# clouds_v30.net
KiCad netlist of a schematic drawn in EAGLE
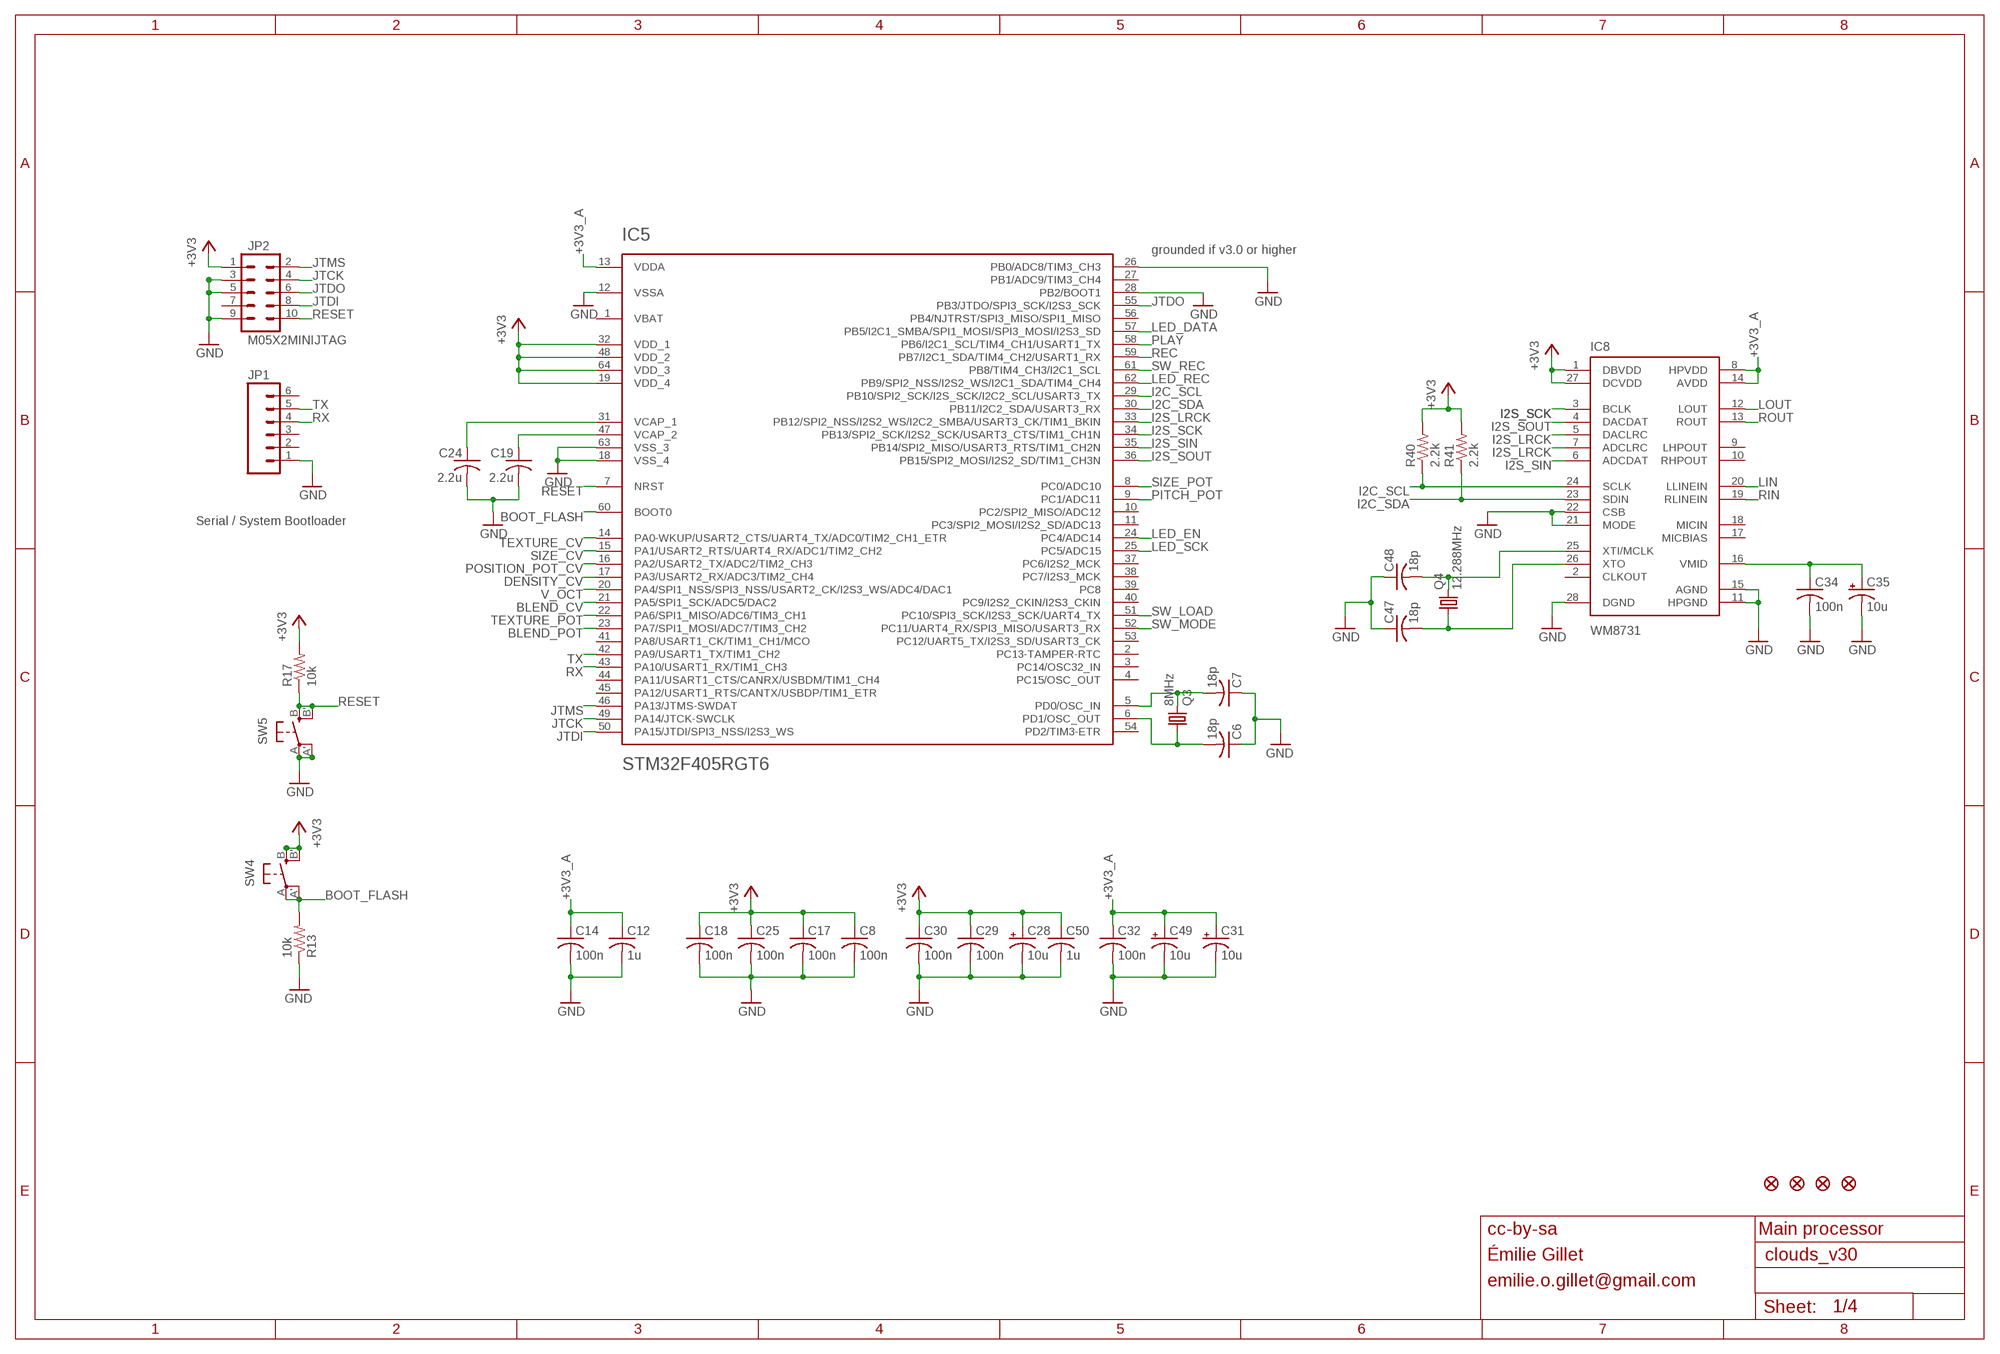
[diagram p0: schematic, sheet 1]
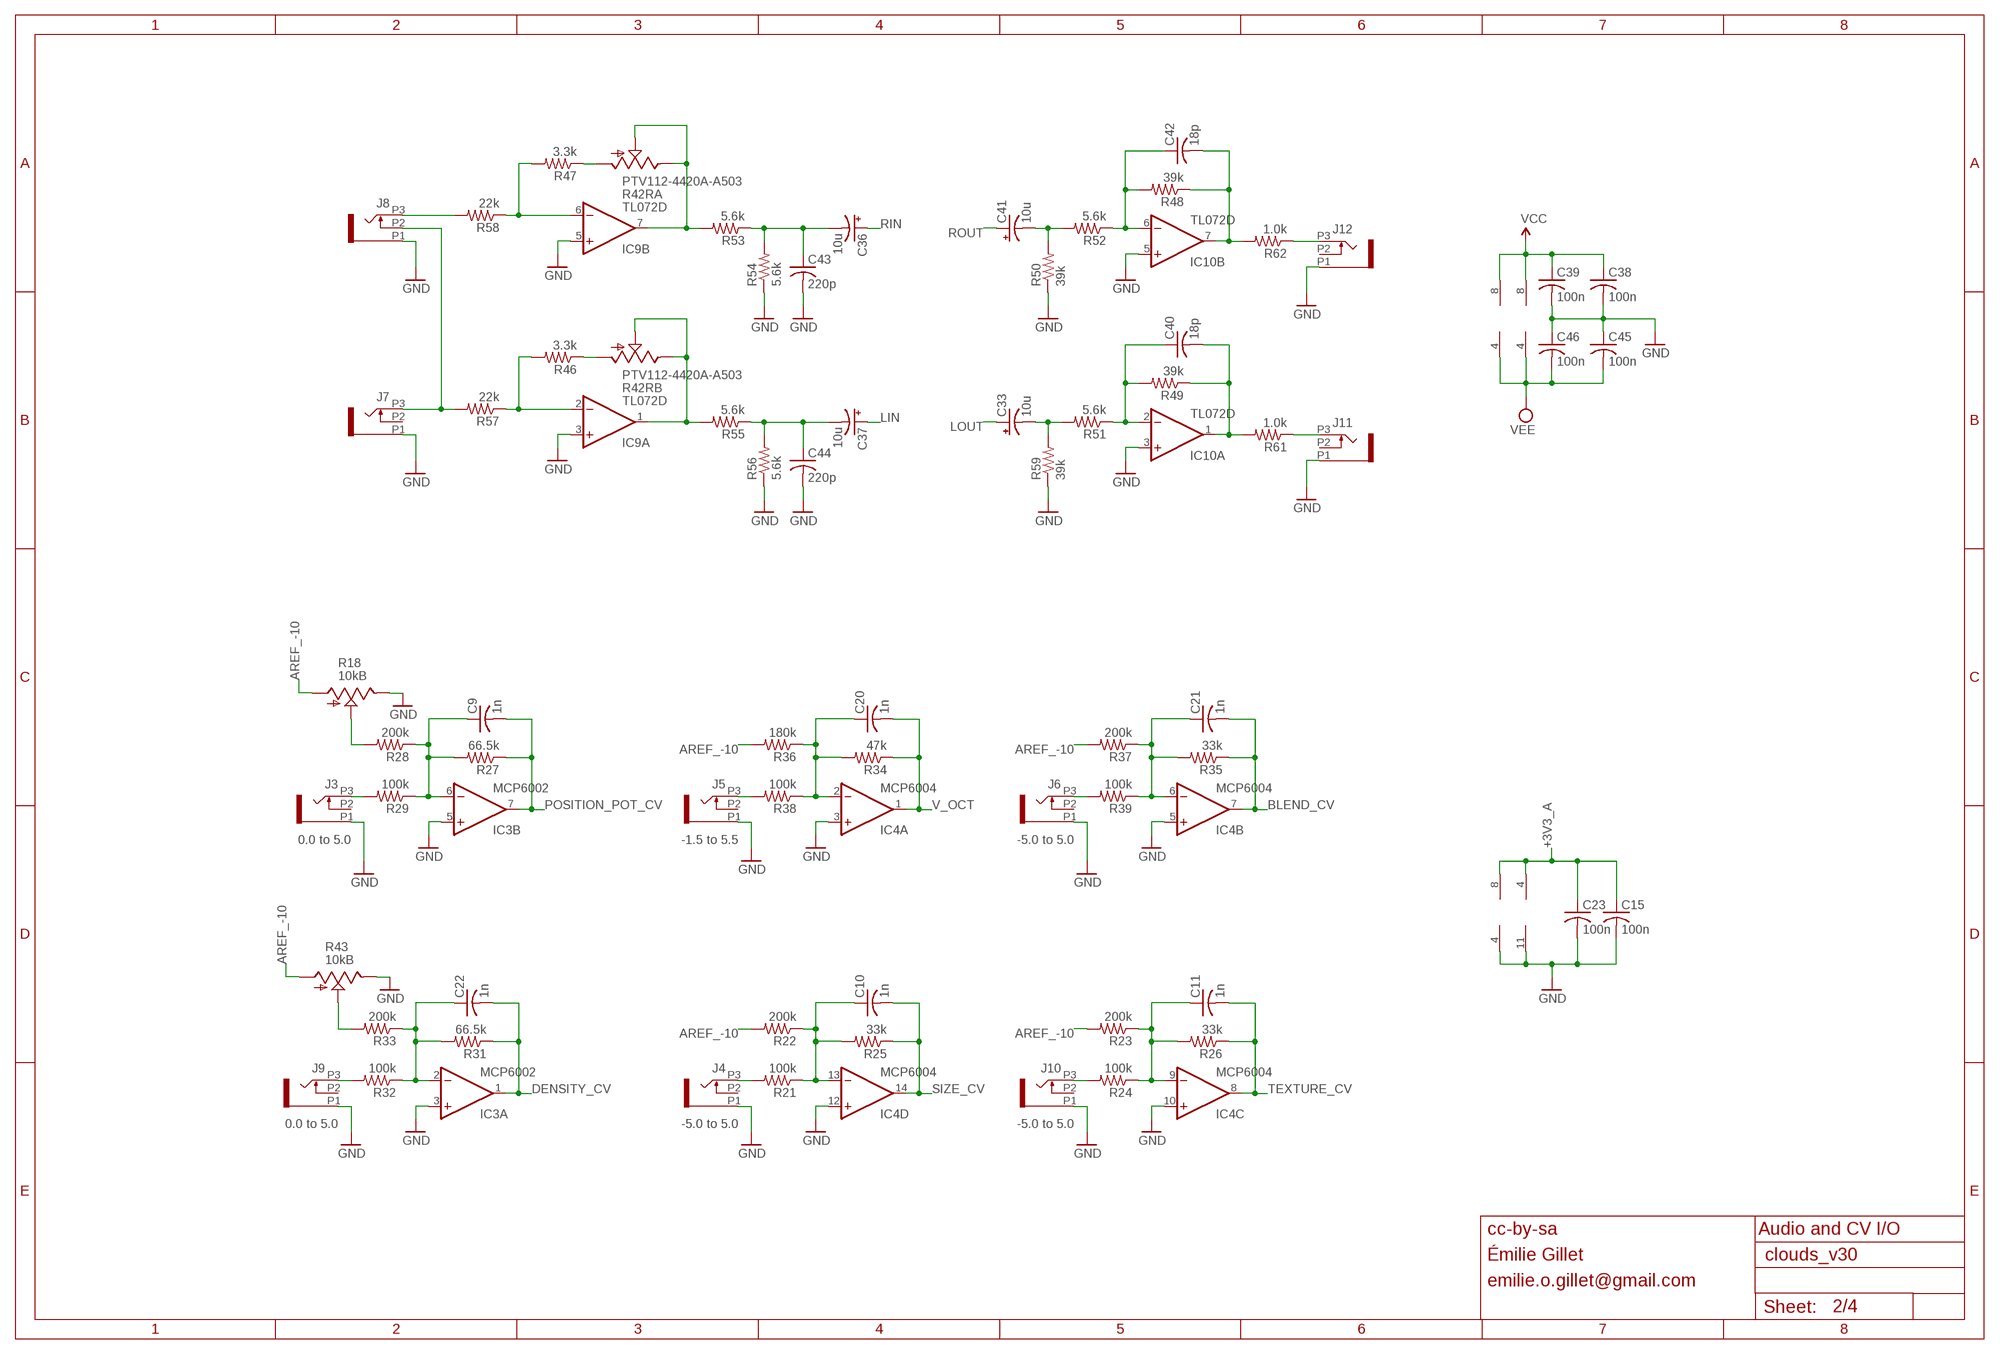
[diagram p1: schematic, sheet 2]
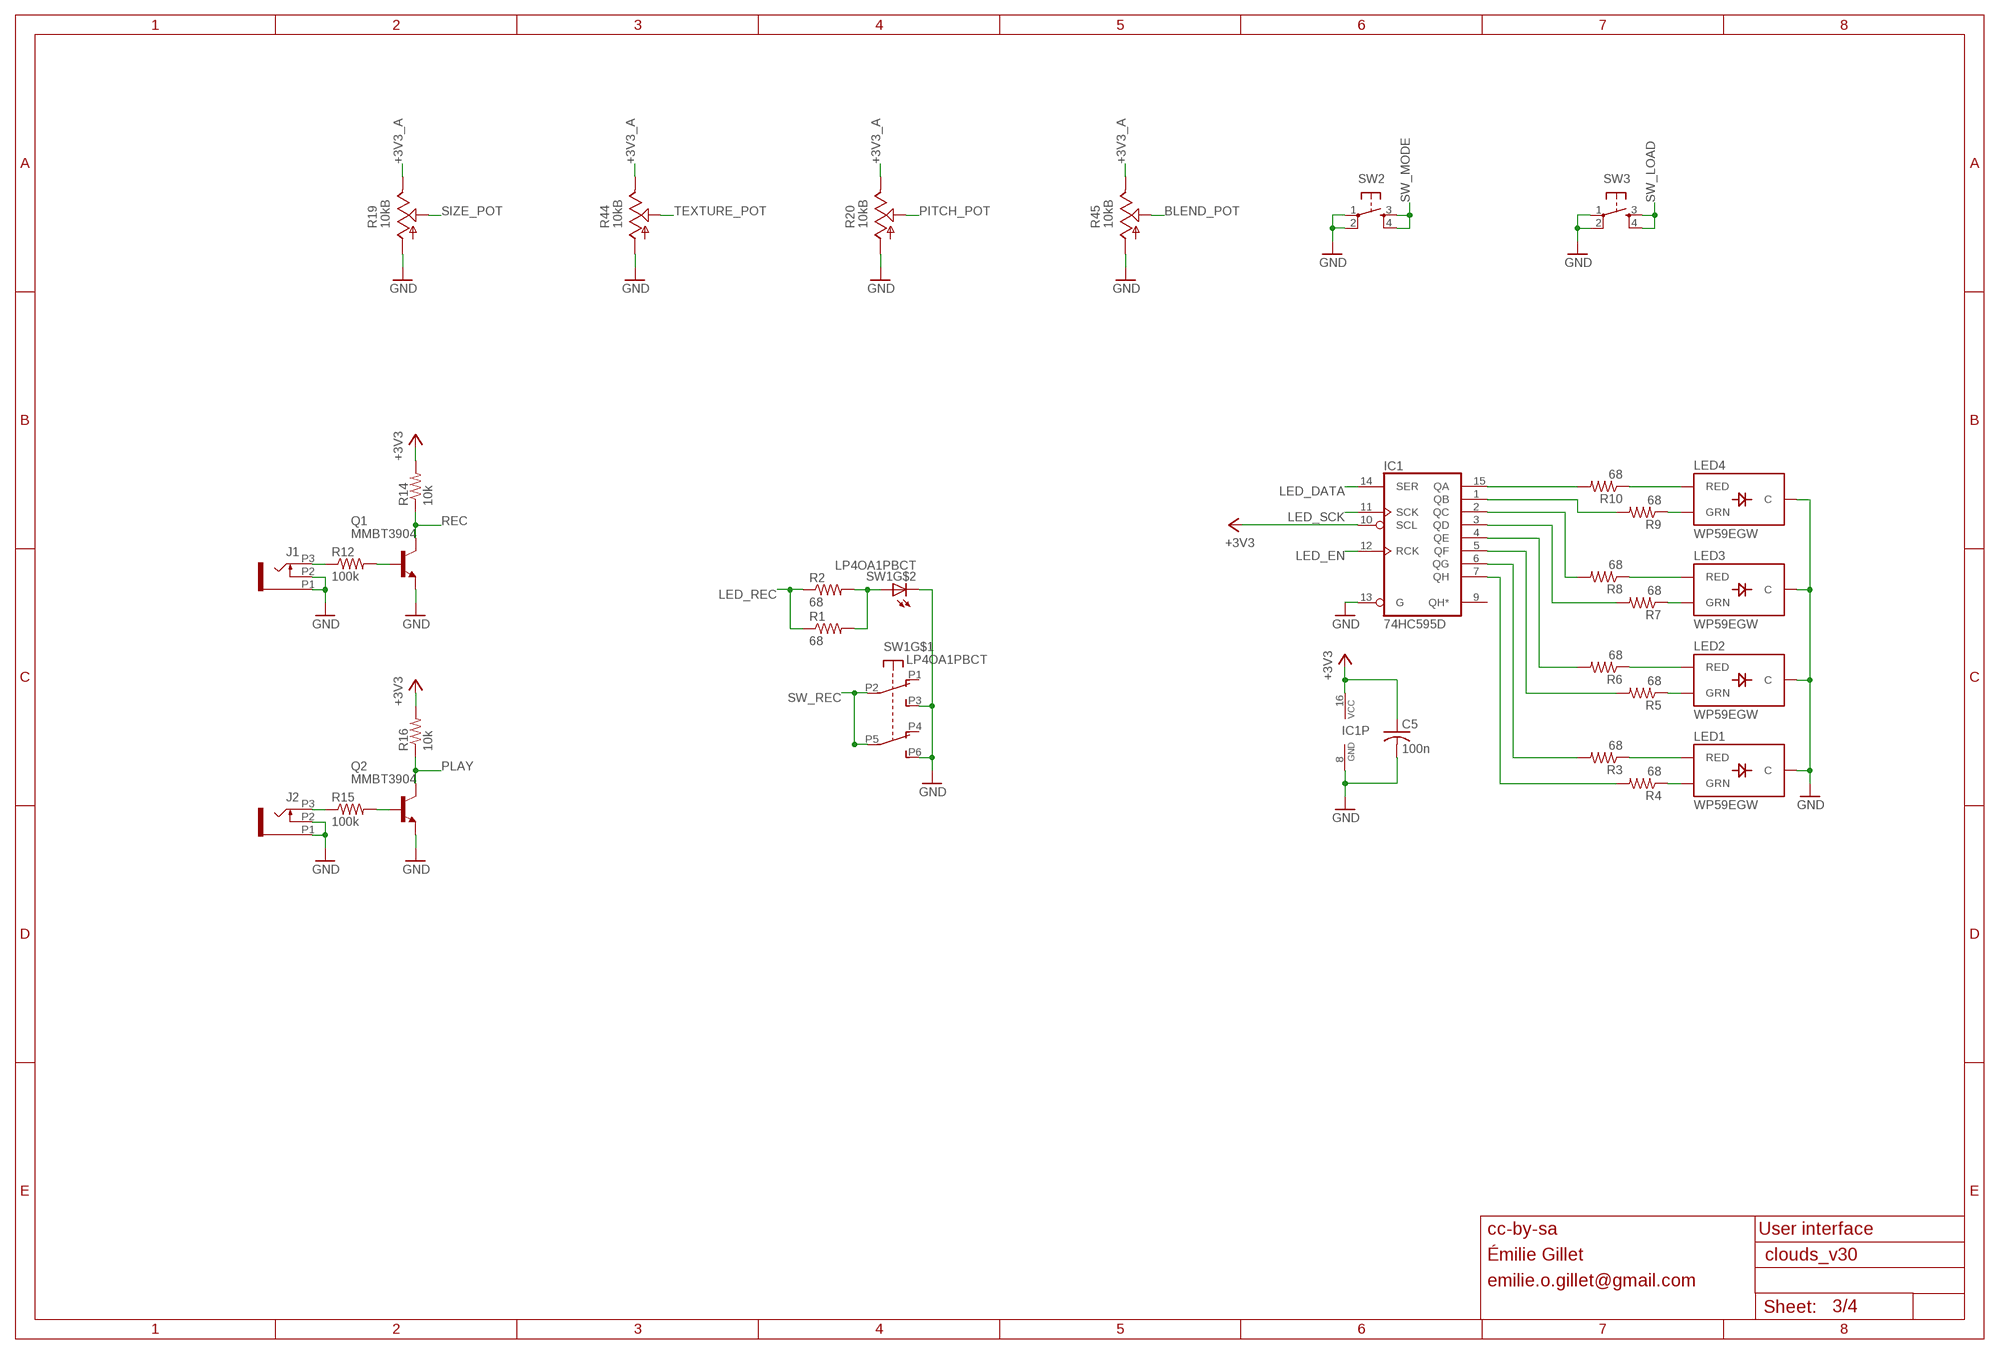
[diagram p2: schematic, sheet 3]
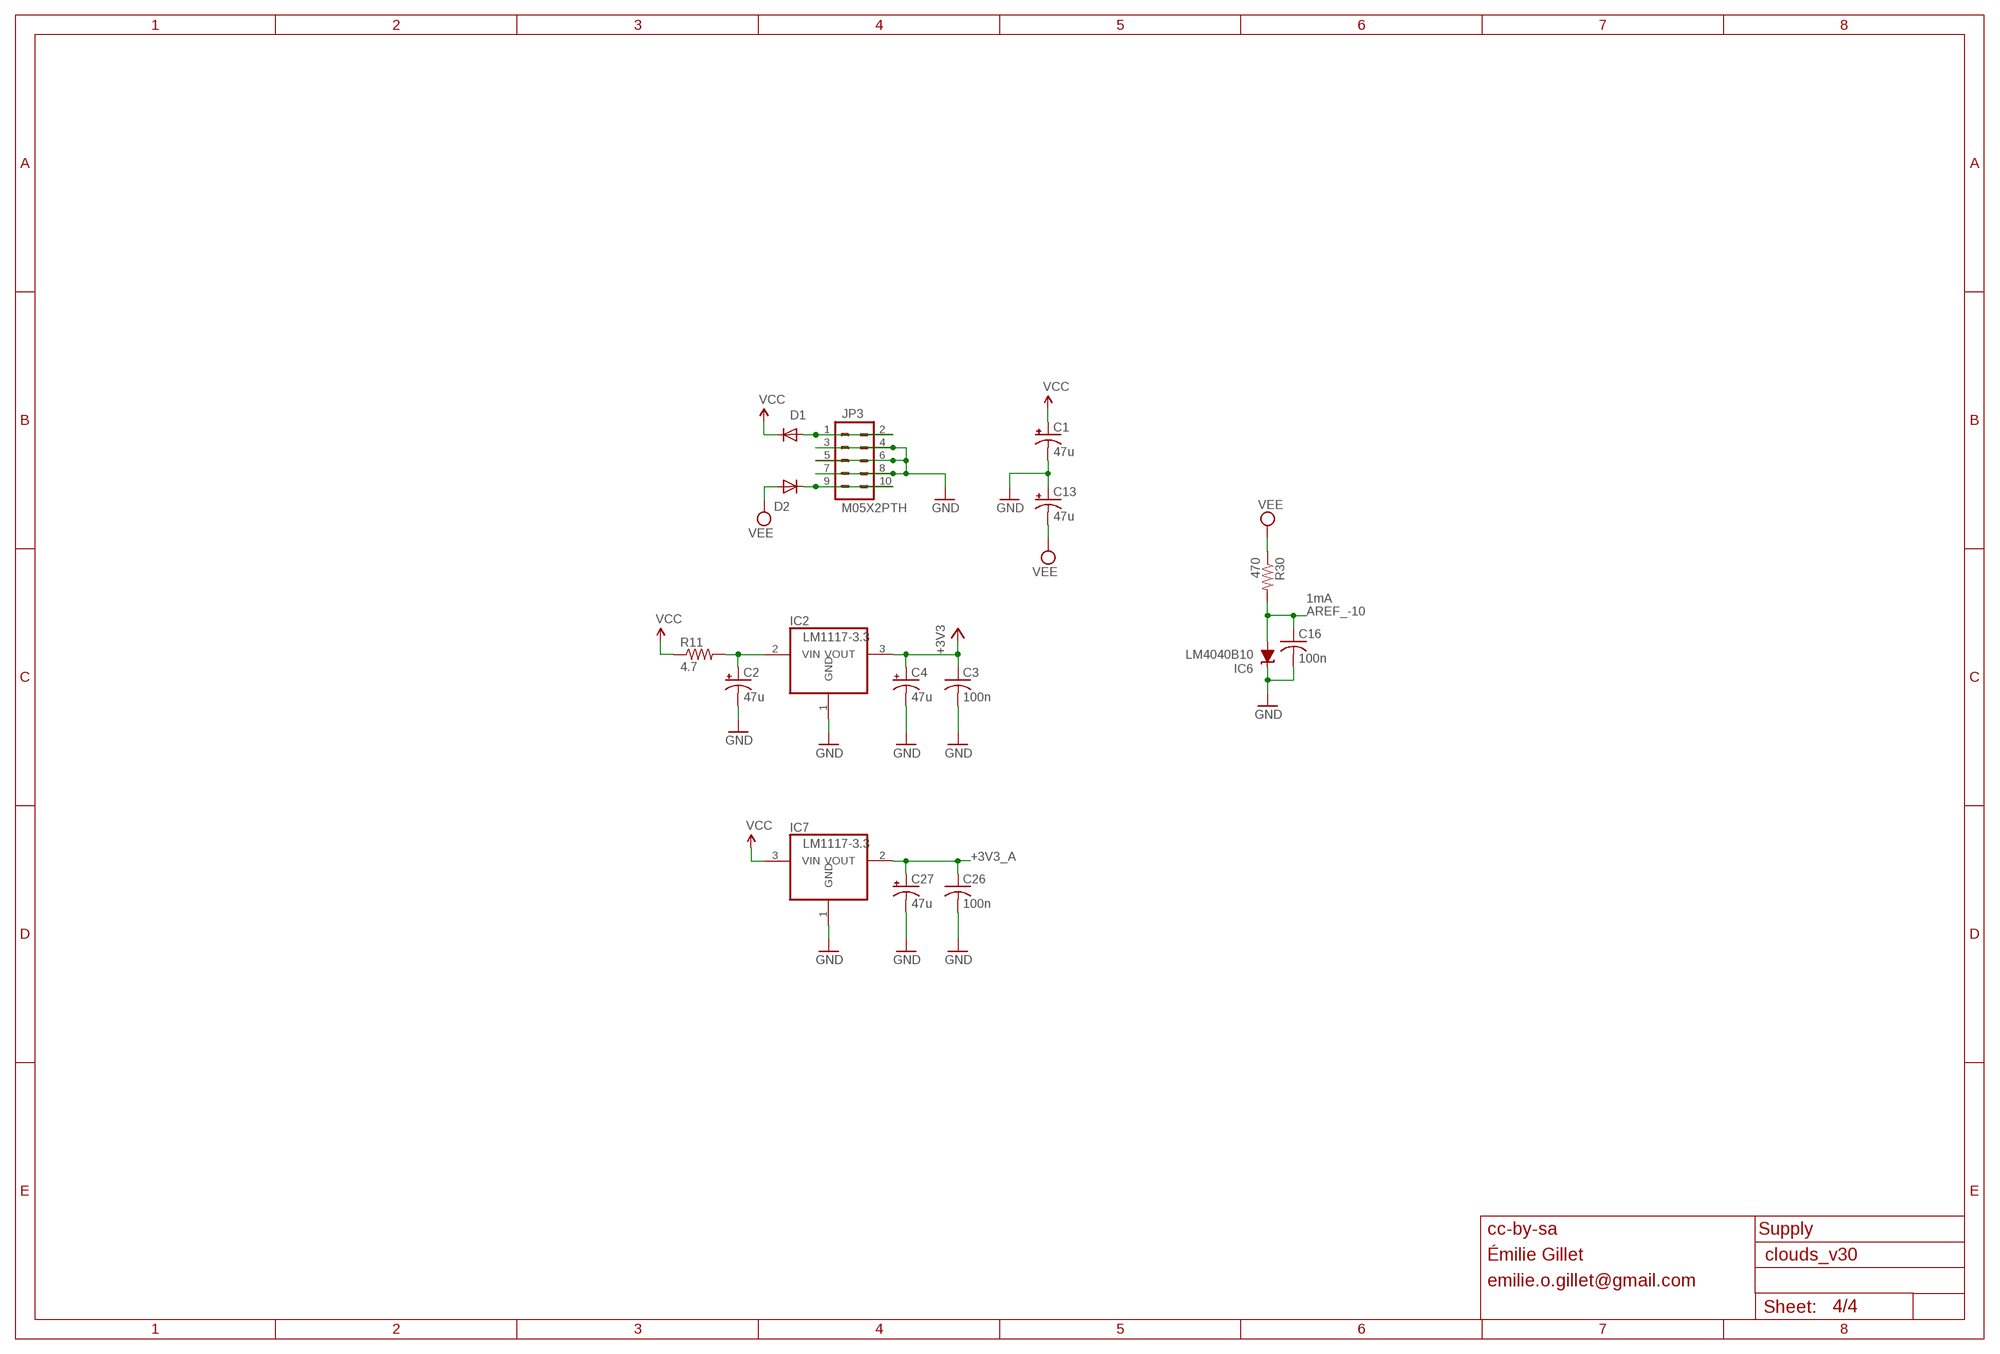
[diagram p3: schematic, sheet 4]

(export (version "E")
  (design (tool "Eeschema 10.0.6"))
  (components
    (comp (ref "C9")
      (value "1n")
      (footprint "eagle-import:C0603")
      (libsource (lib "eagle-import") (part "C-USC0603"))
    )
    (comp (ref "C10")
      (value "1n")
      (footprint "eagle-import:C0603")
      (libsource (lib "eagle-import") (part "C-USC0603"))
    )
    (comp (ref "C11")
      (value "1n")
      (footprint "eagle-import:C0603")
      (libsource (lib "eagle-import") (part "C-USC0603"))
    )
    (comp (ref "C15")
      (value "100n")
      (footprint "eagle-import:C0603")
      (libsource (lib "eagle-import") (part "C-USC0603"))
    )
    (comp (ref "C20")
      (value "1n")
      (footprint "eagle-import:C0603")
      (libsource (lib "eagle-import") (part "C-USC0603"))
    )
    (comp (ref "C21")
      (value "1n")
      (footprint "eagle-import:C0603")
      (libsource (lib "eagle-import") (part "C-USC0603"))
    )
    (comp (ref "C22")
      (value "1n")
      (footprint "eagle-import:C0603")
      (libsource (lib "eagle-import") (part "C-USC0603"))
    )
    (comp (ref "C23")
      (value "100n")
      (footprint "eagle-import:C0603")
      (libsource (lib "eagle-import") (part "C-USC0603"))
    )
    (comp (ref "C33")
      (value "10u")
      (footprint "eagle-import:PANASONIC_B")
      (libsource (lib "eagle-import") (part "CPOL-USB"))
    )
    (comp (ref "C36")
      (value "10u")
      (footprint "eagle-import:PANASONIC_B")
      (libsource (lib "eagle-import") (part "CPOL-USB"))
    )
    (comp (ref "C37")
      (value "10u")
      (footprint "eagle-import:PANASONIC_B")
      (libsource (lib "eagle-import") (part "CPOL-USB"))
    )
    (comp (ref "C38")
      (value "100n")
      (footprint "eagle-import:C0603")
      (libsource (lib "eagle-import") (part "C-USC0603"))
    )
    (comp (ref "C39")
      (value "100n")
      (footprint "eagle-import:C0603")
      (libsource (lib "eagle-import") (part "C-USC0603"))
    )
    (comp (ref "C40")
      (value "18p")
      (footprint "eagle-import:C0603")
      (libsource (lib "eagle-import") (part "C-USC0603"))
    )
    (comp (ref "C41")
      (value "10u")
      (footprint "eagle-import:PANASONIC_B")
      (libsource (lib "eagle-import") (part "CPOL-USB"))
    )
    (comp (ref "C42")
      (value "18p")
      (footprint "eagle-import:C0603")
      (libsource (lib "eagle-import") (part "C-USC0603"))
    )
    (comp (ref "C43")
      (value "220p")
      (footprint "eagle-import:C0603")
      (libsource (lib "eagle-import") (part "C-USC0603"))
    )
    (comp (ref "C44")
      (value "220p")
      (footprint "eagle-import:C0603")
      (libsource (lib "eagle-import") (part "C-USC0603"))
    )
    (comp (ref "C45")
      (value "100n")
      (footprint "eagle-import:C0603")
      (libsource (lib "eagle-import") (part "C-USC0603"))
    )
    (comp (ref "C46")
      (value "100n")
      (footprint "eagle-import:C0603")
      (libsource (lib "eagle-import") (part "C-USC0603"))
    )
    (comp (ref "IC3")
      (value "MCP6002")
      (footprint "eagle-import:SO08")
      (libsource (lib "eagle-import") (part "TL072D"))
    )
    (comp (ref "IC4")
      (value "MCP6004")
      (footprint "eagle-import:SO14")
      (libsource (lib "eagle-import") (part "TL074D"))
    )
    (comp (ref "IC9")
      (value "TL072D")
      (footprint "eagle-import:SO08")
      (libsource (lib "eagle-import") (part "og-linear_TL072D"))
    )
    (comp (ref "IC10")
      (value "TL072D")
      (footprint "eagle-import:SO08")
      (libsource (lib "eagle-import") (part "og-linear_TL072D"))
    )
    (comp (ref "J3")
      (value "PJ301_THONKICONN6")
      (footprint "eagle-import:WQP_PJ_301M6")
      (libsource (lib "eagle-import") (part "PJ301_THONKICONN6"))
    )
    (comp (ref "J4")
      (value "PJ301_THONKICONN6")
      (footprint "eagle-import:WQP_PJ_301M6")
      (libsource (lib "eagle-import") (part "PJ301_THONKICONN6"))
    )
    (comp (ref "J5")
      (value "PJ301_THONKICONN6")
      (footprint "eagle-import:WQP_PJ_301M6")
      (libsource (lib "eagle-import") (part "PJ301_THONKICONN6"))
    )
    (comp (ref "J6")
      (value "PJ301_THONKICONN6")
      (footprint "eagle-import:WQP_PJ_301M6")
      (libsource (lib "eagle-import") (part "PJ301_THONKICONN6"))
    )
    (comp (ref "J7")
      (value "PJ301_THONKICONN6")
      (footprint "eagle-import:WQP_PJ_301M6")
      (libsource (lib "eagle-import") (part "PJ301_THONKICONN6"))
    )
    (comp (ref "J8")
      (value "PJ301_THONKICONN6")
      (footprint "eagle-import:WQP_PJ_301M6")
      (libsource (lib "eagle-import") (part "PJ301_THONKICONN6"))
    )
    (comp (ref "J9")
      (value "PJ301_THONKICONN6")
      (footprint "eagle-import:WQP_PJ_301M6")
      (libsource (lib "eagle-import") (part "PJ301_THONKICONN6"))
    )
    (comp (ref "J10")
      (value "PJ301_THONKICONN6")
      (footprint "eagle-import:WQP_PJ_301M6")
      (libsource (lib "eagle-import") (part "PJ301_THONKICONN6"))
    )
    (comp (ref "J11")
      (value "PJ301_THONKICONN6")
      (footprint "eagle-import:WQP_PJ_301M6")
      (libsource (lib "eagle-import") (part "PJ301_THONKICONN6"))
    )
    (comp (ref "J12")
      (value "PJ301_THONKICONN6")
      (footprint "eagle-import:WQP_PJ_301M6")
      (libsource (lib "eagle-import") (part "PJ301_THONKICONN6"))
    )
    (comp (ref "R18")
      (value "10kB")
      (footprint "eagle-import:ALPS_POT_VERTICAL_PS")
      (libsource (lib "eagle-import") (part "POT_USVERTICAL_PS"))
    )
    (comp (ref "R21")
      (value "100k")
      (footprint "eagle-import:R0603")
      (libsource (lib "eagle-import") (part "R-US_R0603"))
    )
    (comp (ref "R22")
      (value "200k")
      (footprint "eagle-import:R0603")
      (libsource (lib "eagle-import") (part "R-US_R0603"))
    )
    (comp (ref "R23")
      (value "200k")
      (footprint "eagle-import:R0603")
      (libsource (lib "eagle-import") (part "R-US_R0603"))
    )
    (comp (ref "R24")
      (value "100k")
      (footprint "eagle-import:R0603")
      (libsource (lib "eagle-import") (part "R-US_R0603"))
    )
    (comp (ref "R25")
      (value "33k")
      (footprint "eagle-import:R0603")
      (libsource (lib "eagle-import") (part "R-US_R0603"))
    )
    (comp (ref "R26")
      (value "33k")
      (footprint "eagle-import:R0603")
      (libsource (lib "eagle-import") (part "R-US_R0603"))
    )
    (comp (ref "R27")
      (value "66.5k")
      (footprint "eagle-import:R0603")
      (libsource (lib "eagle-import") (part "R-US_R0603"))
    )
    (comp (ref "R28")
      (value "200k")
      (footprint "eagle-import:R0603")
      (libsource (lib "eagle-import") (part "R-US_R0603"))
    )
    (comp (ref "R29")
      (value "100k")
      (footprint "eagle-import:R0603")
      (libsource (lib "eagle-import") (part "R-US_R0603"))
    )
    (comp (ref "R31")
      (value "66.5k")
      (footprint "eagle-import:R0603")
      (libsource (lib "eagle-import") (part "R-US_R0603"))
    )
    (comp (ref "R32")
      (value "100k")
      (footprint "eagle-import:R0603")
      (libsource (lib "eagle-import") (part "R-US_R0603"))
    )
    (comp (ref "R33")
      (value "200k")
      (footprint "eagle-import:R0603")
      (libsource (lib "eagle-import") (part "R-US_R0603"))
    )
    (comp (ref "R34")
      (value "47k")
      (footprint "eagle-import:R0603")
      (libsource (lib "eagle-import") (part "R-US_R0603"))
    )
    (comp (ref "R35")
      (value "33k")
      (footprint "eagle-import:R0603")
      (libsource (lib "eagle-import") (part "R-US_R0603"))
    )
    (comp (ref "R36")
      (value "180k")
      (footprint "eagle-import:R0603")
      (libsource (lib "eagle-import") (part "R-US_R0603"))
    )
    (comp (ref "R37")
      (value "200k")
      (footprint "eagle-import:R0603")
      (libsource (lib "eagle-import") (part "R-US_R0603"))
    )
    (comp (ref "R38")
      (value "100k")
      (footprint "eagle-import:R0603")
      (libsource (lib "eagle-import") (part "R-US_R0603"))
    )
    (comp (ref "R39")
      (value "100k")
      (footprint "eagle-import:R0603")
      (libsource (lib "eagle-import") (part "R-US_R0603"))
    )
    (comp (ref "R42")
      (value "PTV112-4420A-A503")
      (footprint "eagle-import:BOURNS_PTV112")
      (libsource (lib "eagle-import") (part "POT_US_DUAL_GANG"))
    )
    (comp (ref "R43")
      (value "10kB")
      (footprint "eagle-import:ALPS_POT_VERTICAL_PS")
      (libsource (lib "eagle-import") (part "POT_USVERTICAL_PS"))
    )
    (comp (ref "R46")
      (value "3.3k")
      (footprint "eagle-import:R0603")
      (libsource (lib "eagle-import") (part "R-US_R0603"))
    )
    (comp (ref "R47")
      (value "3.3k")
      (footprint "eagle-import:R0603")
      (libsource (lib "eagle-import") (part "R-US_R0603"))
    )
    (comp (ref "R48")
      (value "39k")
      (footprint "eagle-import:R0603")
      (libsource (lib "eagle-import") (part "R-US_R0603"))
    )
    (comp (ref "R49")
      (value "39k")
      (footprint "eagle-import:R0603")
      (libsource (lib "eagle-import") (part "R-US_R0603"))
    )
    (comp (ref "R50")
      (value "39k")
      (footprint "eagle-import:R0603")
      (libsource (lib "eagle-import") (part "R-US_R0603"))
    )
    (comp (ref "R51")
      (value "5.6k")
      (footprint "eagle-import:R0603")
      (libsource (lib "eagle-import") (part "R-US_R0603"))
    )
    (comp (ref "R52")
      (value "5.6k")
      (footprint "eagle-import:R0603")
      (libsource (lib "eagle-import") (part "R-US_R0603"))
    )
    (comp (ref "R53")
      (value "5.6k")
      (footprint "eagle-import:R0603")
      (libsource (lib "eagle-import") (part "R-US_R0603"))
    )
    (comp (ref "R54")
      (value "5.6k")
      (footprint "eagle-import:R0603")
      (libsource (lib "eagle-import") (part "R-US_R0603"))
    )
    (comp (ref "R55")
      (value "5.6k")
      (footprint "eagle-import:R0603")
      (libsource (lib "eagle-import") (part "R-US_R0603"))
    )
    (comp (ref "R56")
      (value "5.6k")
      (footprint "eagle-import:R0603")
      (libsource (lib "eagle-import") (part "R-US_R0603"))
    )
    (comp (ref "R57")
      (value "22k")
      (footprint "eagle-import:R0603")
      (libsource (lib "eagle-import") (part "R-US_R0603"))
    )
    (comp (ref "R58")
      (value "22k")
      (footprint "eagle-import:R0603")
      (libsource (lib "eagle-import") (part "R-US_R0603"))
    )
    (comp (ref "R59")
      (value "39k")
      (footprint "eagle-import:R0603")
      (libsource (lib "eagle-import") (part "R-US_R0603"))
    )
    (comp (ref "R61")
      (value "1.0k")
      (footprint "eagle-import:R0603")
      (libsource (lib "eagle-import") (part "R-US_R0603"))
    )
    (comp (ref "R62")
      (value "1.0k")
      (footprint "eagle-import:R0603")
      (libsource (lib "eagle-import") (part "R-US_R0603"))
    )
    (comp (ref "C6")
      (value "18p")
      (footprint "eagle-import:C0603")
      (libsource (lib "eagle-import") (part "C-USC0603"))
    )
    (comp (ref "C7")
      (value "18p")
      (footprint "eagle-import:C0603")
      (libsource (lib "eagle-import") (part "C-USC0603"))
    )
    (comp (ref "C8")
      (value "100n")
      (footprint "eagle-import:C0603")
      (libsource (lib "eagle-import") (part "C-USC0603"))
    )
    (comp (ref "C12")
      (value "1u")
      (footprint "eagle-import:C0603")
      (libsource (lib "eagle-import") (part "C-USC0603"))
    )
    (comp (ref "C14")
      (value "100n")
      (footprint "eagle-import:C0603")
      (libsource (lib "eagle-import") (part "C-USC0603"))
    )
    (comp (ref "C17")
      (value "100n")
      (footprint "eagle-import:C0603")
      (libsource (lib "eagle-import") (part "C-USC0603"))
    )
    (comp (ref "C18")
      (value "100n")
      (footprint "eagle-import:C0603")
      (libsource (lib "eagle-import") (part "C-USC0603"))
    )
    (comp (ref "C19")
      (value "2.2u")
      (footprint "eagle-import:C0805")
      (libsource (lib "eagle-import") (part "C-USC0805"))
    )
    (comp (ref "C24")
      (value "2.2u")
      (footprint "eagle-import:C0805")
      (libsource (lib "eagle-import") (part "C-USC0805"))
    )
    (comp (ref "C25")
      (value "100n")
      (footprint "eagle-import:C0603")
      (libsource (lib "eagle-import") (part "C-USC0603"))
    )
    (comp (ref "C28")
      (value "10u")
      (footprint "eagle-import:PANASONIC_A")
      (libsource (lib "eagle-import") (part "CPOL-USA"))
    )
    (comp (ref "C29")
      (value "100n")
      (footprint "eagle-import:C0603")
      (libsource (lib "eagle-import") (part "C-USC0603"))
    )
    (comp (ref "C30")
      (value "100n")
      (footprint "eagle-import:C0603")
      (libsource (lib "eagle-import") (part "C-USC0603"))
    )
    (comp (ref "C31")
      (value "10u")
      (footprint "eagle-import:PANASONIC_B")
      (libsource (lib "eagle-import") (part "CPOL-USB"))
    )
    (comp (ref "C32")
      (value "100n")
      (footprint "eagle-import:C0603")
      (libsource (lib "eagle-import") (part "C-USC0603"))
    )
    (comp (ref "C34")
      (value "100n")
      (footprint "eagle-import:C0603")
      (libsource (lib "eagle-import") (part "C-USC0603"))
    )
    (comp (ref "C35")
      (value "10u")
      (footprint "eagle-import:PANASONIC_B")
      (libsource (lib "eagle-import") (part "CPOL-USB"))
    )
    (comp (ref "C47")
      (value "18p")
      (footprint "eagle-import:C0603")
      (libsource (lib "eagle-import") (part "C-USC0603"))
    )
    (comp (ref "C48")
      (value "18p")
      (footprint "eagle-import:C0603")
      (libsource (lib "eagle-import") (part "C-USC0603"))
    )
    (comp (ref "C49")
      (value "10u")
      (footprint "eagle-import:PANASONIC_A")
      (libsource (lib "eagle-import") (part "CPOL-USA"))
    )
    (comp (ref "C50")
      (value "1u")
      (footprint "eagle-import:C0603")
      (libsource (lib "eagle-import") (part "C-USC0603"))
    )
    (comp (ref "F1")
      (value "FIDUCIAL1X2")
      (footprint "eagle-import:FIDUCIAL-1X2")
      (libsource (lib "eagle-import") (part "FIDUCIAL1X2"))
    )
    (comp (ref "F2")
      (value "FIDUCIAL1X2")
      (footprint "eagle-import:FIDUCIAL-1X2")
      (libsource (lib "eagle-import") (part "FIDUCIAL1X2"))
    )
    (comp (ref "F3")
      (value "FIDUCIAL1X2")
      (footprint "eagle-import:FIDUCIAL-1X2")
      (libsource (lib "eagle-import") (part "FIDUCIAL1X2"))
    )
    (comp (ref "F4")
      (value "FIDUCIAL1X2")
      (footprint "eagle-import:FIDUCIAL-1X2")
      (libsource (lib "eagle-import") (part "FIDUCIAL1X2"))
    )
    (comp (ref "IC5")
      (value "STM32F405RGT6")
      (footprint "eagle-import:TQFP-10X10-64")
      (libsource (lib "eagle-import") (part "STM32F20X"))
    )
    (comp (ref "IC8")
      (value "WM8731")
      (footprint "eagle-import:SSOP28")
      (libsource (lib "eagle-import") (part "WM8731"))
    )
    (comp (ref "JP1")
      (value "M06SIP")
      (footprint "eagle-import:1X06")
      (libsource (lib "eagle-import") (part "M06SIP"))
    )
    (comp (ref "JP2")
      (value "M05X2MINIJTAG")
      (footprint "eagle-import:2X5-1.27")
      (libsource (lib "eagle-import") (part "M05X2MINIJTAG"))
    )
    (comp (ref "Q3")
      (value "8MHz")
      (footprint "eagle-import:HC49UP")
      (libsource (lib "eagle-import") (part "CRYSTALHC49UP"))
    )
    (comp (ref "Q4")
      (value "12.288MHz")
      (footprint "eagle-import:HC49UP")
      (libsource (lib "eagle-import") (part "CRYSTALHC49UP"))
    )
    (comp (ref "R13")
      (value "10k")
      (footprint "eagle-import:R0603")
      (libsource (lib "eagle-import") (part "R-US_R0603"))
    )
    (comp (ref "R17")
      (value "10k")
      (footprint "eagle-import:R0603")
      (libsource (lib "eagle-import") (part "R-US_R0603"))
    )
    (comp (ref "R40")
      (value "2.2k")
      (footprint "eagle-import:R0603")
      (libsource (lib "eagle-import") (part "R-US_R0603"))
    )
    (comp (ref "R41")
      (value "2.2k")
      (footprint "eagle-import:R0603")
      (libsource (lib "eagle-import") (part "R-US_R0603"))
    )
    (comp (ref "SW4")
      (value "EVQQ2")
      (footprint "eagle-import:EVQ-Q2")
      (libsource (lib "eagle-import") (part "EVQQ2"))
    )
    (comp (ref "SW5")
      (value "EVQQ2")
      (footprint "eagle-import:EVQ-Q2")
      (libsource (lib "eagle-import") (part "EVQQ2"))
    )
    (comp (ref "C1")
      (value "47u")
      (footprint "eagle-import:PANASONIC_D")
      (libsource (lib "eagle-import") (part "CPOL-USD"))
    )
    (comp (ref "C2")
      (value "47u")
      (footprint "eagle-import:PANASONIC_D")
      (libsource (lib "eagle-import") (part "CPOL-USD"))
    )
    (comp (ref "C3")
      (value "100n")
      (footprint "eagle-import:C0603")
      (libsource (lib "eagle-import") (part "C-USC0603"))
    )
    (comp (ref "C4")
      (value "47u")
      (footprint "eagle-import:PANASONIC_D")
      (libsource (lib "eagle-import") (part "CPOL-USD"))
    )
    (comp (ref "C13")
      (value "47u")
      (footprint "eagle-import:PANASONIC_D")
      (libsource (lib "eagle-import") (part "CPOL-USD"))
    )
    (comp (ref "C16")
      (value "100n")
      (footprint "eagle-import:C0603")
      (libsource (lib "eagle-import") (part "C-USC0603"))
    )
    (comp (ref "C26")
      (value "100n")
      (footprint "eagle-import:C0603")
      (libsource (lib "eagle-import") (part "C-USC0603"))
    )
    (comp (ref "C27")
      (value "47u")
      (footprint "eagle-import:PANASONIC_D")
      (libsource (lib "eagle-import") (part "CPOL-USD"))
    )
    (comp (ref "D1")
      (value "1N5819HW")
      (footprint "eagle-import:SOD123")
      (libsource (lib "eagle-import") (part "DIODE-SOD123"))
    )
    (comp (ref "D2")
      (value "1N5819HW")
      (footprint "eagle-import:SOD123")
      (libsource (lib "eagle-import") (part "DIODE-SOD123"))
    )
    (comp (ref "IC2")
      (value "LM1117-3.3")
      (footprint "eagle-import:TO252")
      (libsource (lib "eagle-import") (part "REG1117T"))
    )
    (comp (ref "IC6")
      (value "LM4040B10")
      (footprint "eagle-import:DBZ_R-PDSO-G3")
      (libsource (lib "eagle-import") (part "LM4041DBZB12"))
    )
    (comp (ref "IC7")
      (value "LM1117-3.3")
      (footprint "eagle-import:SOT223")
      (libsource (lib "eagle-import") (part "REG1117"))
    )
    (comp (ref "JP3")
      (value "M05X2PTH")
      (footprint "eagle-import:AVR_ICSP")
      (libsource (lib "eagle-import") (part "M05X2PTH"))
    )
    (comp (ref "R11")
      (value "4.7")
      (footprint "eagle-import:R1206")
      (libsource (lib "eagle-import") (part "R-US_R1206"))
    )
    (comp (ref "R30")
      (value "470")
      (footprint "eagle-import:R0603")
      (libsource (lib "eagle-import") (part "R-US_R0603"))
    )
    (comp (ref "C5")
      (value "100n")
      (footprint "eagle-import:C0603")
      (libsource (lib "eagle-import") (part "C-USC0603"))
    )
    (comp (ref "IC1")
      (value "74HC595D")
      (footprint "eagle-import:SO16")
      (libsource (lib "eagle-import") (part "74595DHC"))
    )
    (comp (ref "J1")
      (value "PJ301_THONKICONN6")
      (footprint "eagle-import:WQP_PJ_301M6")
      (libsource (lib "eagle-import") (part "PJ301_THONKICONN6"))
    )
    (comp (ref "J2")
      (value "PJ301_THONKICONN6")
      (footprint "eagle-import:WQP_PJ_301M6")
      (libsource (lib "eagle-import") (part "PJ301_THONKICONN6"))
    )
    (comp (ref "LED1")
      (value "WP59EGW")
      (footprint "eagle-import:LED-BICOLOR-THROUGHHOLE-5MM")
      (libsource (lib "eagle-import") (part "LED-BICOLOR-THROUGHHOLE5MM"))
    )
    (comp (ref "LED2")
      (value "WP59EGW")
      (footprint "eagle-import:LED-BICOLOR-THROUGHHOLE-5MM")
      (libsource (lib "eagle-import") (part "LED-BICOLOR-THROUGHHOLE5MM"))
    )
    (comp (ref "LED3")
      (value "WP59EGW")
      (footprint "eagle-import:LED-BICOLOR-THROUGHHOLE-5MM")
      (libsource (lib "eagle-import") (part "LED-BICOLOR-THROUGHHOLE5MM"))
    )
    (comp (ref "LED4")
      (value "WP59EGW")
      (footprint "eagle-import:LED-BICOLOR-THROUGHHOLE-5MM")
      (libsource (lib "eagle-import") (part "LED-BICOLOR-THROUGHHOLE5MM"))
    )
    (comp (ref "Q1")
      (value "MMBT3904")
      (footprint "eagle-import:SOT23-BEC")
      (libsource (lib "eagle-import") (part "-NPN-SOT23-BECMMBT3904LT1"))
    )
    (comp (ref "Q2")
      (value "MMBT3904")
      (footprint "eagle-import:SOT23-BEC")
      (libsource (lib "eagle-import") (part "-NPN-SOT23-BECMMBT3904LT1"))
    )
    (comp (ref "R1")
      (value "68")
      (footprint "eagle-import:R0603")
      (libsource (lib "eagle-import") (part "R-US_R0603"))
    )
    (comp (ref "R2")
      (value "68")
      (footprint "eagle-import:R0603")
      (libsource (lib "eagle-import") (part "R-US_R0603"))
    )
    (comp (ref "R3")
      (value "68")
      (footprint "eagle-import:R0603")
      (libsource (lib "eagle-import") (part "R-US_R0603"))
    )
    (comp (ref "R4")
      (value "68")
      (footprint "eagle-import:R0603")
      (libsource (lib "eagle-import") (part "R-US_R0603"))
    )
    (comp (ref "R5")
      (value "68")
      (footprint "eagle-import:R0603")
      (libsource (lib "eagle-import") (part "R-US_R0603"))
    )
    (comp (ref "R6")
      (value "68")
      (footprint "eagle-import:R0603")
      (libsource (lib "eagle-import") (part "R-US_R0603"))
    )
    (comp (ref "R7")
      (value "68")
      (footprint "eagle-import:R0603")
      (libsource (lib "eagle-import") (part "R-US_R0603"))
    )
    (comp (ref "R8")
      (value "68")
      (footprint "eagle-import:R0603")
      (libsource (lib "eagle-import") (part "R-US_R0603"))
    )
    (comp (ref "R9")
      (value "68")
      (footprint "eagle-import:R0603")
      (libsource (lib "eagle-import") (part "R-US_R0603"))
    )
    (comp (ref "R10")
      (value "68")
      (footprint "eagle-import:R0603")
      (libsource (lib "eagle-import") (part "R-US_R0603"))
    )
    (comp (ref "R12")
      (value "100k")
      (footprint "eagle-import:R0603")
      (libsource (lib "eagle-import") (part "R-US_R0603"))
    )
    (comp (ref "R14")
      (value "10k")
      (footprint "eagle-import:R0603")
      (libsource (lib "eagle-import") (part "R-US_R0603"))
    )
    (comp (ref "R15")
      (value "100k")
      (footprint "eagle-import:R0603")
      (libsource (lib "eagle-import") (part "R-US_R0603"))
    )
    (comp (ref "R16")
      (value "10k")
      (footprint "eagle-import:R0603")
      (libsource (lib "eagle-import") (part "R-US_R0603"))
    )
    (comp (ref "R19")
      (value "10kB")
      (footprint "eagle-import:ALPS_POT_VERTICAL_PS")
      (libsource (lib "eagle-import") (part "POT_USVERTICAL_PS"))
    )
    (comp (ref "R20")
      (value "10kB")
      (footprint "eagle-import:ALPS_POT_VERTICAL_PS")
      (libsource (lib "eagle-import") (part "POT_USVERTICAL_PS"))
    )
    (comp (ref "R44")
      (value "10kB")
      (footprint "eagle-import:ALPS_POT_VERTICAL_PS")
      (libsource (lib "eagle-import") (part "POT_USVERTICAL_PS"))
    )
    (comp (ref "R45")
      (value "10kB")
      (footprint "eagle-import:ALPS_POT_VERTICAL_PS")
      (libsource (lib "eagle-import") (part "POT_USVERTICAL_PS"))
    )
    (comp (ref "SW1")
      (value "LP4OA1PBCT")
      (footprint "eagle-import:LP4OA1PBCT")
      (libsource (lib "eagle-import") (part "LP4OA1PBCT"))
    )
    (comp (ref "SW2")
      (value "TAC_SWITCHPTH")
      (footprint "eagle-import:TACTILE-PTH")
      (libsource (lib "eagle-import") (part "TAC_SWITCHPTH"))
    )
    (comp (ref "SW3")
      (value "TAC_SWITCHPTH")
      (footprint "eagle-import:TACTILE-PTH")
      (libsource (lib "eagle-import") (part "TAC_SWITCHPTH"))
    )
  )
  (nets
    (net (code "1") (name "+3V3") (class "Default")
      (node (ref "C17") (pin "1") (pinfunction "1_1") (pintype "passive"))
      (node (ref "C18") (pin "1") (pinfunction "1_1") (pintype "passive"))
      (node (ref "C25") (pin "1") (pinfunction "1_1") (pintype "passive"))
      (node (ref "C28") (pin "+") (pinfunction "+_+") (pintype "passive"))
      (node (ref "C29") (pin "1") (pinfunction "1_1") (pintype "passive"))
      (node (ref "C3") (pin "1") (pinfunction "1_1") (pintype "passive"))
      (node (ref "C30") (pin "1") (pinfunction "1_1") (pintype "passive"))
      (node (ref "C4") (pin "+") (pinfunction "+_+") (pintype "passive"))
      (node (ref "C5") (pin "1") (pinfunction "1_1") (pintype "passive"))
      (node (ref "C50") (pin "1") (pinfunction "1_1") (pintype "passive"))
      (node (ref "C8") (pin "1") (pinfunction "1_1") (pintype "passive"))
      (node (ref "IC1") (pin "10") (pinfunction "SCL_10") (pintype "input"))
      (node (ref "IC1") (pin "16") (pinfunction "VCC_16") (pintype "power_in"))
      (node (ref "IC2") (pin "3") (pinfunction "VOUT_3") (pintype "output"))
      (node (ref "IC5") (pin "19") (pinfunction "VDD_4_19") (pintype "power_in"))
      (node (ref "IC5") (pin "32") (pinfunction "VDD_1_32") (pintype "power_in"))
      (node (ref "IC5") (pin "48") (pinfunction "VDD_2_48") (pintype "power_in"))
      (node (ref "IC5") (pin "64") (pinfunction "VDD_3_64") (pintype "power_in"))
      (node (ref "IC8") (pin "1") (pinfunction "DBVDD_1") (pintype "bidirectional"))
      (node (ref "IC8") (pin "27") (pinfunction "DCVDD_27") (pintype "bidirectional"))
      (node (ref "JP2") (pin "1") (pinfunction "1_1") (pintype "passive"))
      (node (ref "R14") (pin "2") (pinfunction "2_2") (pintype "passive"))
      (node (ref "R16") (pin "2") (pinfunction "2_2") (pintype "passive"))
      (node (ref "R17") (pin "2") (pinfunction "2_2") (pintype "passive"))
      (node (ref "R40") (pin "2") (pinfunction "2_2") (pintype "passive"))
      (node (ref "R41") (pin "2") (pinfunction "2_2") (pintype "passive"))
      (node (ref "SW4") (pin "B") (pinfunction "S_B") (pintype "passive"))
      (node (ref "SW4") (pin "B'") (pinfunction "S1_B'") (pintype "passive"))
    )
    (net (code "2") (name "+3V3_A") (class "Default")
      (node (ref "C12") (pin "1") (pinfunction "1_1") (pintype "passive"))
      (node (ref "C14") (pin "1") (pinfunction "1_1") (pintype "passive"))
      (node (ref "C15") (pin "1") (pinfunction "1_1") (pintype "passive"))
      (node (ref "C23") (pin "1") (pinfunction "1_1") (pintype "passive"))
      (node (ref "C26") (pin "1") (pinfunction "1_1") (pintype "passive"))
      (node (ref "C27") (pin "+") (pinfunction "+_+") (pintype "passive"))
      (node (ref "C31") (pin "+") (pinfunction "+_+") (pintype "passive"))
      (node (ref "C32") (pin "1") (pinfunction "1_1") (pintype "passive"))
      (node (ref "C49") (pin "+") (pinfunction "+_+") (pintype "passive"))
      (node (ref "IC3") (pin "8") (pinfunction "V+_8") (pintype "power_in"))
      (node (ref "IC4") (pin "4") (pinfunction "V+_4") (pintype "power_in"))
      (node (ref "IC5") (pin "13") (pinfunction "VDDA_13") (pintype "power_in"))
      (node (ref "IC7") (pin "2") (pinfunction "VOUT_2") (pintype "output"))
      (node (ref "IC8") (pin "14") (pinfunction "AVDD_14") (pintype "bidirectional"))
      (node (ref "IC8") (pin "8") (pinfunction "HPVDD_8") (pintype "bidirectional"))
      (node (ref "R19") (pin "P$1") (pinfunction "E_P$1") (pintype "passive"))
      (node (ref "R20") (pin "P$1") (pinfunction "E_P$1") (pintype "passive"))
      (node (ref "R44") (pin "P$1") (pinfunction "E_P$1") (pintype "passive"))
      (node (ref "R45") (pin "P$1") (pinfunction "E_P$1") (pintype "passive"))
    )
    (net (code "3") (name "AREF_-10") (class "Default")
      (node (ref "C16") (pin "1") (pinfunction "1_1") (pintype "passive"))
      (node (ref "IC6") (pin "2") (pinfunction "A_2") (pintype "passive"))
      (node (ref "R18") (pin "P$3") (pinfunction "A_P$3") (pintype "passive"))
      (node (ref "R22") (pin "2") (pinfunction "2_2") (pintype "passive"))
      (node (ref "R23") (pin "2") (pinfunction "2_2") (pintype "passive"))
      (node (ref "R30") (pin "2") (pinfunction "2_2") (pintype "passive"))
      (node (ref "R36") (pin "2") (pinfunction "2_2") (pintype "passive"))
      (node (ref "R37") (pin "2") (pinfunction "2_2") (pintype "passive"))
      (node (ref "R43") (pin "P$3") (pinfunction "A_P$3") (pintype "passive"))
    )
    (net (code "4") (name "BLEND_CV") (class "Default")
      (node (ref "C21") (pin "2") (pinfunction "2_2") (pintype "passive"))
      (node (ref "IC4") (pin "7") (pinfunction "OUT_7") (pintype "output"))
      (node (ref "IC5") (pin "21") (pinfunction "PA5/SPI1_SCK/ADC5/DAC2_21") (pintype "bidirectional"))
      (node (ref "R35") (pin "1") (pinfunction "1_1") (pintype "passive"))
    )
    (net (code "5") (name "BLEND_POT") (class "Default")
      (node (ref "IC5") (pin "23") (pinfunction "PA7/SPI1_MOSI/ADC7/TIM3_CH2_23") (pintype "bidirectional"))
      (node (ref "R45") (pin "P$2") (pinfunction "S_P$2") (pintype "passive"))
    )
    (net (code "6") (name "BOOT_FLASH") (class "Default")
      (node (ref "IC5") (pin "60") (pinfunction "BOOT0_60") (pintype "bidirectional"))
      (node (ref "R13") (pin "2") (pinfunction "2_2") (pintype "passive"))
      (node (ref "SW4") (pin "A") (pinfunction "P_A") (pintype "passive"))
      (node (ref "SW4") (pin "A'") (pinfunction "P1_A'") (pintype "passive"))
    )
    (net (code "7") (name "DENSITY_CV") (class "Default")
      (node (ref "C22") (pin "2") (pinfunction "2_2") (pintype "passive"))
      (node (ref "IC3") (pin "1") (pinfunction "OUT_1") (pintype "output"))
      (node (ref "IC5") (pin "17") (pinfunction "PA3/USART2_RX/ADC3/TIM2_CH4_17") (pintype "bidirectional"))
      (node (ref "R31") (pin "1") (pinfunction "1_1") (pintype "passive"))
    )
    (net (code "8") (name "GND") (class "Default")
      (node (ref "C1") (pin "-") (pinfunction "-_-") (pintype "passive"))
      (node (ref "C12") (pin "2") (pinfunction "2_2") (pintype "passive"))
      (node (ref "C13") (pin "+") (pinfunction "+_+") (pintype "passive"))
      (node (ref "C14") (pin "2") (pinfunction "2_2") (pintype "passive"))
      (node (ref "C15") (pin "2") (pinfunction "2_2") (pintype "passive"))
      (node (ref "C16") (pin "2") (pinfunction "2_2") (pintype "passive"))
      (node (ref "C17") (pin "2") (pinfunction "2_2") (pintype "passive"))
      (node (ref "C18") (pin "2") (pinfunction "2_2") (pintype "passive"))
      (node (ref "C19") (pin "2") (pinfunction "2_2") (pintype "passive"))
      (node (ref "C2") (pin "-") (pinfunction "-_-") (pintype "passive"))
      (node (ref "C23") (pin "2") (pinfunction "2_2") (pintype "passive"))
      (node (ref "C24") (pin "2") (pinfunction "2_2") (pintype "passive"))
      (node (ref "C25") (pin "2") (pinfunction "2_2") (pintype "passive"))
      (node (ref "C26") (pin "2") (pinfunction "2_2") (pintype "passive"))
      (node (ref "C27") (pin "-") (pinfunction "-_-") (pintype "passive"))
      (node (ref "C28") (pin "-") (pinfunction "-_-") (pintype "passive"))
      (node (ref "C29") (pin "2") (pinfunction "2_2") (pintype "passive"))
      (node (ref "C3") (pin "2") (pinfunction "2_2") (pintype "passive"))
      (node (ref "C30") (pin "2") (pinfunction "2_2") (pintype "passive"))
      (node (ref "C31") (pin "-") (pinfunction "-_-") (pintype "passive"))
      (node (ref "C32") (pin "2") (pinfunction "2_2") (pintype "passive"))
      (node (ref "C34") (pin "2") (pinfunction "2_2") (pintype "passive"))
      (node (ref "C35") (pin "-") (pinfunction "-_-") (pintype "passive"))
      (node (ref "C38") (pin "2") (pinfunction "2_2") (pintype "passive"))
      (node (ref "C39") (pin "2") (pinfunction "2_2") (pintype "passive"))
      (node (ref "C4") (pin "-") (pinfunction "-_-") (pintype "passive"))
      (node (ref "C43") (pin "2") (pinfunction "2_2") (pintype "passive"))
      (node (ref "C44") (pin "2") (pinfunction "2_2") (pintype "passive"))
      (node (ref "C45") (pin "1") (pinfunction "1_1") (pintype "passive"))
      (node (ref "C46") (pin "1") (pinfunction "1_1") (pintype "passive"))
      (node (ref "C47") (pin "1") (pinfunction "1_1") (pintype "passive"))
      (node (ref "C48") (pin "1") (pinfunction "1_1") (pintype "passive"))
      (node (ref "C49") (pin "-") (pinfunction "-_-") (pintype "passive"))
      (node (ref "C5") (pin "2") (pinfunction "2_2") (pintype "passive"))
      (node (ref "C50") (pin "2") (pinfunction "2_2") (pintype "passive"))
      (node (ref "C6") (pin "1") (pinfunction "1_1") (pintype "passive"))
      (node (ref "C7") (pin "1") (pinfunction "1_1") (pintype "passive"))
      (node (ref "C8") (pin "2") (pinfunction "2_2") (pintype "passive"))
      (node (ref "IC1") (pin "13") (pinfunction "G_13") (pintype "input"))
      (node (ref "IC1") (pin "8") (pinfunction "GND_8") (pintype "power_in"))
      (node (ref "IC10") (pin "3") (pinfunction "+IN_3") (pintype "input"))
      (node (ref "IC10") (pin "5") (pinfunction "+IN_5") (pintype "input"))
      (node (ref "IC2") (pin "1") (pinfunction "GND_1") (pintype "power_in"))
      (node (ref "IC3") (pin "3") (pinfunction "+IN_3") (pintype "input"))
      (node (ref "IC3") (pin "4") (pinfunction "V-_4") (pintype "power_in"))
      (node (ref "IC3") (pin "5") (pinfunction "+IN_5") (pintype "input"))
      (node (ref "IC4") (pin "10") (pinfunction "+IN_10") (pintype "input"))
      (node (ref "IC4") (pin "11") (pinfunction "V-_11") (pintype "power_in"))
      (node (ref "IC4") (pin "12") (pinfunction "+IN_12") (pintype "input"))
      (node (ref "IC4") (pin "3") (pinfunction "+IN_3") (pintype "input"))
      (node (ref "IC4") (pin "5") (pinfunction "+IN_5") (pintype "input"))
      (node (ref "IC5") (pin "12") (pinfunction "VSSA_12") (pintype "power_in"))
      (node (ref "IC5") (pin "18") (pinfunction "VSS_4_18") (pintype "power_in"))
      (node (ref "IC5") (pin "26") (pinfunction "PB0/ADC8/TIM3_CH3_26") (pintype "bidirectional"))
      (node (ref "IC5") (pin "28") (pinfunction "PB2/BOOT1_28") (pintype "bidirectional"))
      (node (ref "IC5") (pin "63") (pinfunction "VSS_3_63") (pintype "power_in"))
      (node (ref "IC6") (pin "1") (pinfunction "C_1") (pintype "passive"))
      (node (ref "IC7") (pin "1") (pinfunction "GND_1") (pintype "power_in"))
      (node (ref "IC8") (pin "11") (pinfunction "HPGND_11") (pintype "bidirectional"))
      (node (ref "IC8") (pin "15") (pinfunction "AGND_15") (pintype "bidirectional"))
      (node (ref "IC8") (pin "21") (pinfunction "MODE_21") (pintype "bidirectional"))
      (node (ref "IC8") (pin "22") (pinfunction "CSB_22") (pintype "bidirectional"))
      (node (ref "IC8") (pin "28") (pinfunction "DGND_28") (pintype "bidirectional"))
      (node (ref "IC9") (pin "3") (pinfunction "+IN_3") (pintype "input"))
      (node (ref "IC9") (pin "5") (pinfunction "+IN_5") (pintype "input"))
      (node (ref "J1") (pin "P1") (pinfunction "1_P1") (pintype "passive"))
      (node (ref "J1") (pin "P2") (pinfunction "2_P2") (pintype "passive"))
      (node (ref "J10") (pin "P1") (pinfunction "1_P1") (pintype "passive"))
      (node (ref "J11") (pin "P1") (pinfunction "1_P1") (pintype "passive"))
      (node (ref "J12") (pin "P1") (pinfunction "1_P1") (pintype "passive"))
      (node (ref "J2") (pin "P1") (pinfunction "1_P1") (pintype "passive"))
      (node (ref "J2") (pin "P2") (pinfunction "2_P2") (pintype "passive"))
      (node (ref "J3") (pin "P1") (pinfunction "1_P1") (pintype "passive"))
      (node (ref "J4") (pin "P1") (pinfunction "1_P1") (pintype "passive"))
      (node (ref "J5") (pin "P1") (pinfunction "1_P1") (pintype "passive"))
      (node (ref "J6") (pin "P1") (pinfunction "1_P1") (pintype "passive"))
      (node (ref "J7") (pin "P1") (pinfunction "1_P1") (pintype "passive"))
      (node (ref "J8") (pin "P1") (pinfunction "1_P1") (pintype "passive"))
      (node (ref "J9") (pin "P1") (pinfunction "1_P1") (pintype "passive"))
      (node (ref "JP1") (pin "1") (pinfunction "1_1") (pintype "passive"))
      (node (ref "JP2") (pin "3") (pinfunction "3_3") (pintype "passive"))
      (node (ref "JP2") (pin "5") (pinfunction "5_5") (pintype "passive"))
      (node (ref "JP2") (pin "9") (pinfunction "9_9") (pintype "passive"))
      (node (ref "JP3") (pin "3") (pinfunction "3_3") (pintype "passive"))
      (node (ref "JP3") (pin "4") (pinfunction "4_4") (pintype "passive"))
      (node (ref "JP3") (pin "5") (pinfunction "5_5") (pintype "passive"))
      (node (ref "JP3") (pin "6") (pinfunction "6_6") (pintype "passive"))
      (node (ref "JP3") (pin "7") (pinfunction "7_7") (pintype "passive"))
      (node (ref "JP3") (pin "8") (pinfunction "8_8") (pintype "passive"))
      (node (ref "LED1") (pin "2") (pinfunction "C_2") (pintype "bidirectional"))
      (node (ref "LED2") (pin "2") (pinfunction "C_2") (pintype "bidirectional"))
      (node (ref "LED3") (pin "2") (pinfunction "C_2") (pintype "bidirectional"))
      (node (ref "LED4") (pin "2") (pinfunction "C_2") (pintype "bidirectional"))
      (node (ref "Q1") (pin "E") (pinfunction "E_E") (pintype "passive"))
      (node (ref "Q2") (pin "E") (pinfunction "E_E") (pintype "passive"))
      (node (ref "R13") (pin "1") (pinfunction "1_1") (pintype "passive"))
      (node (ref "R18") (pin "P$1") (pinfunction "E_P$1") (pintype "passive"))
      (node (ref "R19") (pin "P$3") (pinfunction "A_P$3") (pintype "passive"))
      (node (ref "R20") (pin "P$3") (pinfunction "A_P$3") (pintype "passive"))
      (node (ref "R43") (pin "P$1") (pinfunction "E_P$1") (pintype "passive"))
      (node (ref "R44") (pin "P$3") (pinfunction "A_P$3") (pintype "passive"))
      (node (ref "R45") (pin "P$3") (pinfunction "A_P$3") (pintype "passive"))
      (node (ref "R50") (pin "1") (pinfunction "1_1") (pintype "passive"))
      (node (ref "R54") (pin "1") (pinfunction "1_1") (pintype "passive"))
      (node (ref "R56") (pin "1") (pinfunction "1_1") (pintype "passive"))
      (node (ref "R59") (pin "1") (pinfunction "1_1") (pintype "passive"))
      (node (ref "SW1") (pin "L2") (pinfunction "L2_L2") (pintype "passive"))
      (node (ref "SW1") (pin "P3") (pinfunction "A3_P3") (pintype "passive"))
      (node (ref "SW1") (pin "P6") (pinfunction "B3_P6") (pintype "passive"))
      (node (ref "SW2") (pin "1") (pinfunction "1_1") (pintype "passive"))
      (node (ref "SW2") (pin "2") (pinfunction "2_2") (pintype "passive"))
      (node (ref "SW3") (pin "1") (pinfunction "1_1") (pintype "passive"))
      (node (ref "SW3") (pin "2") (pinfunction "2_2") (pintype "passive"))
      (node (ref "SW5") (pin "A") (pinfunction "P_A") (pintype "passive"))
      (node (ref "SW5") (pin "A'") (pinfunction "P1_A'") (pintype "passive"))
    )
    (net (code "9") (name "I2C_SCL") (class "Default")
      (node (ref "IC5") (pin "29") (pinfunction "PB10/SPI2_SCK/I2S_SCK/I2C2_SCL/USART3_TX_29") (pintype "bidirectional"))
      (node (ref "IC8") (pin "24") (pinfunction "SCLK_24") (pintype "bidirectional"))
      (node (ref "R40") (pin "1") (pinfunction "1_1") (pintype "passive"))
    )
    (net (code "10") (name "I2C_SDA") (class "Default")
      (node (ref "IC5") (pin "30") (pinfunction "PB11/I2C2_SDA/USART3_RX_30") (pintype "bidirectional"))
      (node (ref "IC8") (pin "23") (pinfunction "SDIN_23") (pintype "bidirectional"))
      (node (ref "R41") (pin "1") (pinfunction "1_1") (pintype "passive"))
    )
    (net (code "11") (name "I2S_LRCK") (class "Default")
      (node (ref "IC5") (pin "33") (pinfunction "PB12/SPI2_NSS/I2S2_WS/I2C2_SMBA/USART3_CK/TIM1_BKIN_33") (pintype "bidirectional"))
      (node (ref "IC8") (pin "5") (pinfunction "DACLRC_5") (pintype "bidirectional"))
      (node (ref "IC8") (pin "7") (pinfunction "ADCLRC_7") (pintype "bidirectional"))
    )
    (net (code "12") (name "I2S_SCK") (class "Default")
      (node (ref "IC5") (pin "34") (pinfunction "PB13/SPI2_SCK/I2S2_SCK/USART3_CTS/TIM1_CH1N_34") (pintype "bidirectional"))
      (node (ref "IC8") (pin "3") (pinfunction "BCLK_3") (pintype "bidirectional"))
    )
    (net (code "13") (name "I2S_SIN") (class "Default")
      (node (ref "IC5") (pin "35") (pinfunction "PB14/SPI2_MISO/USART3_RTS/TIM1_CH2N_35") (pintype "bidirectional"))
      (node (ref "IC8") (pin "6") (pinfunction "ADCDAT_6") (pintype "bidirectional"))
    )
    (net (code "14") (name "I2S_SOUT") (class "Default")
      (node (ref "IC5") (pin "36") (pinfunction "PB15/SPI2_MOSI/I2S2_SD/TIM1_CH3N_36") (pintype "bidirectional"))
      (node (ref "IC8") (pin "4") (pinfunction "DACDAT_4") (pintype "bidirectional"))
    )
    (net (code "15") (name "JTCK") (class "Default")
      (node (ref "IC5") (pin "49") (pinfunction "PA14/JTCK-SWCLK_49") (pintype "bidirectional"))
      (node (ref "JP2") (pin "4") (pinfunction "4_4") (pintype "passive"))
    )
    (net (code "16") (name "JTDI") (class "Default")
      (node (ref "IC5") (pin "50") (pinfunction "PA15/JTDI/SPI3_NSS/I2S3_WS_50") (pintype "bidirectional"))
      (node (ref "JP2") (pin "8") (pinfunction "8_8") (pintype "passive"))
    )
    (net (code "17") (name "JTDO") (class "Default")
      (node (ref "IC5") (pin "55") (pinfunction "PB3/JTDO/SPI3_SCK/I2S3_SCK_55") (pintype "bidirectional"))
      (node (ref "JP2") (pin "6") (pinfunction "6_6") (pintype "passive"))
    )
    (net (code "18") (name "JTMS") (class "Default")
      (node (ref "IC5") (pin "46") (pinfunction "PA13/JTMS-SWDAT_46") (pintype "bidirectional"))
      (node (ref "JP2") (pin "2") (pinfunction "2_2") (pintype "passive"))
    )
    (net (code "19") (name "LED_DATA") (class "Default")
      (node (ref "IC1") (pin "14") (pinfunction "SER_14") (pintype "input"))
      (node (ref "IC5") (pin "57") (pinfunction "PB5/I2C1_SMBA/SPI1_MOSI/SPI3_MOSI/I2S3_SD_57") (pintype "bidirectional"))
    )
    (net (code "20") (name "LED_EN") (class "Default")
      (node (ref "IC1") (pin "12") (pinfunction "RCK_12") (pintype "input"))
      (node (ref "IC5") (pin "24") (pinfunction "PC4/ADC14_24") (pintype "bidirectional"))
    )
    (net (code "21") (name "LED_REC") (class "Default")
      (node (ref "IC5") (pin "62") (pinfunction "PB9/SPI2_NSS/I2S2_WS/I2C1_SDA/TIM4_CH4_62") (pintype "bidirectional"))
      (node (ref "R1") (pin "1") (pinfunction "1_1") (pintype "passive"))
      (node (ref "R2") (pin "1") (pinfunction "1_1") (pintype "passive"))
    )
    (net (code "22") (name "LED_SCK") (class "Default")
      (node (ref "IC1") (pin "11") (pinfunction "SCK_11") (pintype "input"))
      (node (ref "IC5") (pin "25") (pinfunction "PC5/ADC15_25") (pintype "bidirectional"))
    )
    (net (code "23") (name "LIN") (class "Default")
      (node (ref "C37") (pin "+") (pinfunction "+_+") (pintype "passive"))
      (node (ref "IC8") (pin "20") (pinfunction "LLINEIN_20") (pintype "bidirectional"))
    )
    (net (code "24") (name "LOUT") (class "Default")
      (node (ref "C33") (pin "+") (pinfunction "+_+") (pintype "passive"))
      (node (ref "IC8") (pin "12") (pinfunction "LOUT_12") (pintype "bidirectional"))
    )
    (net (code "25") (name "Net-(C33-Pad-)") (class "Default")
      (node (ref "C33") (pin "-") (pinfunction "-_-") (pintype "passive"))
      (node (ref "R51") (pin "2") (pinfunction "2_2") (pintype "passive"))
      (node (ref "R59") (pin "2") (pinfunction "2_2") (pintype "passive"))
    )
    (net (code "26") (name "Net-(C36-Pad-)") (class "Default")
      (node (ref "C36") (pin "-") (pinfunction "-_-") (pintype "passive"))
      (node (ref "C43") (pin "1") (pinfunction "1_1") (pintype "passive"))
      (node (ref "R53") (pin "1") (pinfunction "1_1") (pintype "passive"))
      (node (ref "R54") (pin "2") (pinfunction "2_2") (pintype "passive"))
    )
    (net (code "27") (name "Net-(C37-Pad-)") (class "Default")
      (node (ref "C37") (pin "-") (pinfunction "-_-") (pintype "passive"))
      (node (ref "C44") (pin "1") (pinfunction "1_1") (pintype "passive"))
      (node (ref "R55") (pin "1") (pinfunction "1_1") (pintype "passive"))
      (node (ref "R56") (pin "2") (pinfunction "2_2") (pintype "passive"))
    )
    (net (code "28") (name "Net-(C41-Pad-)") (class "Default")
      (node (ref "C41") (pin "-") (pinfunction "-_-") (pintype "passive"))
      (node (ref "R50") (pin "2") (pinfunction "2_2") (pintype "passive"))
      (node (ref "R52") (pin "2") (pinfunction "2_2") (pintype "passive"))
    )
    (net (code "29") (name "Net-(D1-PadA)") (class "Default")
      (node (ref "D1") (pin "A") (pinfunction "A_A") (pintype "passive"))
      (node (ref "JP3") (pin "1") (pinfunction "1_1") (pintype "passive"))
      (node (ref "JP3") (pin "2") (pinfunction "2_2") (pintype "passive"))
    )
    (net (code "30") (name "Net-(D2-PadC)") (class "Default")
      (node (ref "D2") (pin "C") (pinfunction "C_C") (pintype "passive"))
      (node (ref "JP3") (pin "10") (pinfunction "10_10") (pintype "passive"))
      (node (ref "JP3") (pin "9") (pinfunction "9_9") (pintype "passive"))
    )
    (net (code "31") (name "Net-(IC1A-QA)") (class "Default")
      (node (ref "IC1") (pin "15") (pinfunction "QA_15") (pintype "tri_state"))
      (node (ref "R10") (pin "2") (pinfunction "2_2") (pintype "passive"))
    )
    (net (code "32") (name "Net-(IC1A-QB)") (class "Default")
      (node (ref "IC1") (pin "1") (pinfunction "QB_1") (pintype "tri_state"))
      (node (ref "R9") (pin "2") (pinfunction "2_2") (pintype "passive"))
    )
    (net (code "33") (name "Net-(IC1A-QC)") (class "Default")
      (node (ref "IC1") (pin "2") (pinfunction "QC_2") (pintype "tri_state"))
      (node (ref "R8") (pin "2") (pinfunction "2_2") (pintype "passive"))
    )
    (net (code "34") (name "Net-(IC1A-QD)") (class "Default")
      (node (ref "IC1") (pin "3") (pinfunction "QD_3") (pintype "tri_state"))
      (node (ref "R7") (pin "2") (pinfunction "2_2") (pintype "passive"))
    )
    (net (code "35") (name "Net-(IC1A-QE)") (class "Default")
      (node (ref "IC1") (pin "4") (pinfunction "QE_4") (pintype "tri_state"))
      (node (ref "R6") (pin "2") (pinfunction "2_2") (pintype "passive"))
    )
    (net (code "36") (name "Net-(IC1A-QF)") (class "Default")
      (node (ref "IC1") (pin "5") (pinfunction "QF_5") (pintype "tri_state"))
      (node (ref "R5") (pin "2") (pinfunction "2_2") (pintype "passive"))
    )
    (net (code "37") (name "Net-(IC1A-QG)") (class "Default")
      (node (ref "IC1") (pin "6") (pinfunction "QG_6") (pintype "tri_state"))
      (node (ref "R3") (pin "2") (pinfunction "2_2") (pintype "passive"))
    )
    (net (code "38") (name "Net-(IC1A-QH)") (class "Default")
      (node (ref "IC1") (pin "7") (pinfunction "QH_7") (pintype "tri_state"))
      (node (ref "R4") (pin "2") (pinfunction "2_2") (pintype "passive"))
    )
    (net (code "39") (name "Net-(IC2-VIN)") (class "Default")
      (node (ref "C2") (pin "+") (pinfunction "+_+") (pintype "passive"))
      (node (ref "IC2") (pin "2") (pinfunction "VIN_2") (pintype "input"))
      (node (ref "R11") (pin "2") (pinfunction "2_2") (pintype "passive"))
    )
    (net (code "40") (name "Net-(IC3A--IN)") (class "Default")
      (node (ref "C22") (pin "1") (pinfunction "1_1") (pintype "passive"))
      (node (ref "IC3") (pin "2") (pinfunction "-IN_2") (pintype "input"))
      (node (ref "R31") (pin "2") (pinfunction "2_2") (pintype "passive"))
      (node (ref "R32") (pin "1") (pinfunction "1_1") (pintype "passive"))
      (node (ref "R33") (pin "1") (pinfunction "1_1") (pintype "passive"))
    )
    (net (code "41") (name "Net-(IC3B--IN)") (class "Default")
      (node (ref "C9") (pin "1") (pinfunction "1_1") (pintype "passive"))
      (node (ref "IC3") (pin "6") (pinfunction "-IN_6") (pintype "input"))
      (node (ref "R27") (pin "2") (pinfunction "2_2") (pintype "passive"))
      (node (ref "R28") (pin "1") (pinfunction "1_1") (pintype "passive"))
      (node (ref "R29") (pin "1") (pinfunction "1_1") (pintype "passive"))
    )
    (net (code "42") (name "Net-(IC4A--IN)") (class "Default")
      (node (ref "C20") (pin "1") (pinfunction "1_1") (pintype "passive"))
      (node (ref "IC4") (pin "2") (pinfunction "-IN_2") (pintype "input"))
      (node (ref "R34") (pin "2") (pinfunction "2_2") (pintype "passive"))
      (node (ref "R36") (pin "1") (pinfunction "1_1") (pintype "passive"))
      (node (ref "R38") (pin "1") (pinfunction "1_1") (pintype "passive"))
    )
    (net (code "43") (name "Net-(IC4B--IN)") (class "Default")
      (node (ref "C21") (pin "1") (pinfunction "1_1") (pintype "passive"))
      (node (ref "IC4") (pin "6") (pinfunction "-IN_6") (pintype "input"))
      (node (ref "R35") (pin "2") (pinfunction "2_2") (pintype "passive"))
      (node (ref "R37") (pin "1") (pinfunction "1_1") (pintype "passive"))
      (node (ref "R39") (pin "1") (pinfunction "1_1") (pintype "passive"))
    )
    (net (code "44") (name "Net-(IC4C--IN)") (class "Default")
      (node (ref "C11") (pin "1") (pinfunction "1_1") (pintype "passive"))
      (node (ref "IC4") (pin "9") (pinfunction "-IN_9") (pintype "input"))
      (node (ref "R23") (pin "1") (pinfunction "1_1") (pintype "passive"))
      (node (ref "R24") (pin "1") (pinfunction "1_1") (pintype "passive"))
      (node (ref "R26") (pin "2") (pinfunction "2_2") (pintype "passive"))
    )
    (net (code "45") (name "Net-(IC4D--IN)") (class "Default")
      (node (ref "C10") (pin "1") (pinfunction "1_1") (pintype "passive"))
      (node (ref "IC4") (pin "13") (pinfunction "-IN_13") (pintype "input"))
      (node (ref "R21") (pin "1") (pinfunction "1_1") (pintype "passive"))
      (node (ref "R22") (pin "1") (pinfunction "1_1") (pintype "passive"))
      (node (ref "R25") (pin "2") (pinfunction "2_2") (pintype "passive"))
    )
    (net (code "46") (name "Net-(IC5-PD0{slash}OSC_IN)") (class "Default")
      (node (ref "C7") (pin "2") (pinfunction "2_2") (pintype "passive"))
      (node (ref "IC5") (pin "5") (pinfunction "PD0/OSC_IN_5") (pintype "bidirectional"))
      (node (ref "Q3") (pin "2") (pinfunction "2_2") (pintype "passive"))
    )
    (net (code "47") (name "Net-(IC5-PD1{slash}OSC_OUT)") (class "Default")
      (node (ref "C6") (pin "2") (pinfunction "2_2") (pintype "passive"))
      (node (ref "IC5") (pin "6") (pinfunction "PD1/OSC_OUT_6") (pintype "bidirectional"))
      (node (ref "Q3") (pin "1") (pinfunction "1_1") (pintype "passive"))
    )
    (net (code "48") (name "Net-(IC5-VCAP_1)") (class "Default")
      (node (ref "C24") (pin "1") (pinfunction "1_1") (pintype "passive"))
      (node (ref "IC5") (pin "31") (pinfunction "VCAP_1_31") (pintype "power_in"))
    )
    (net (code "49") (name "Net-(IC5-VCAP_2)") (class "Default")
      (node (ref "C19") (pin "1") (pinfunction "1_1") (pintype "passive"))
      (node (ref "IC5") (pin "47") (pinfunction "VCAP_2_47") (pintype "power_in"))
    )
    (net (code "50") (name "Net-(IC8-VMID)") (class "Default")
      (node (ref "C34") (pin "1") (pinfunction "1_1") (pintype "passive"))
      (node (ref "C35") (pin "+") (pinfunction "+_+") (pintype "passive"))
      (node (ref "IC8") (pin "16") (pinfunction "VMID_16") (pintype "bidirectional"))
    )
    (net (code "51") (name "Net-(IC8-XTI{slash}MCLK)") (class "Default")
      (node (ref "C48") (pin "2") (pinfunction "2_2") (pintype "passive"))
      (node (ref "IC8") (pin "25") (pinfunction "XTI/MCLK_25") (pintype "bidirectional"))
      (node (ref "Q4") (pin "2") (pinfunction "2_2") (pintype "passive"))
    )
    (net (code "52") (name "Net-(IC8-XTO)") (class "Default")
      (node (ref "C47") (pin "2") (pinfunction "2_2") (pintype "passive"))
      (node (ref "IC8") (pin "26") (pinfunction "XTO_26") (pintype "bidirectional"))
      (node (ref "Q4") (pin "1") (pinfunction "1_1") (pintype "passive"))
    )
    (net (code "53") (name "Net-(IC9A--IN)") (class "Default")
      (node (ref "IC9") (pin "2") (pinfunction "-IN_2") (pintype "input"))
      (node (ref "R46") (pin "2") (pinfunction "2_2") (pintype "passive"))
      (node (ref "R57") (pin "1") (pinfunction "1_1") (pintype "passive"))
    )
    (net (code "54") (name "Net-(IC9A-OUT)") (class "Default")
      (node (ref "IC9") (pin "1") (pinfunction "OUT_1") (pintype "output"))
      (node (ref "R42") (pin "2") (pinfunction "S_2") (pintype "passive"))
      (node (ref "R42") (pin "3") (pinfunction "E_3") (pintype "passive"))
      (node (ref "R55") (pin "2") (pinfunction "2_2") (pintype "passive"))
    )
    (net (code "55") (name "Net-(IC9B--IN)") (class "Default")
      (node (ref "IC9") (pin "6") (pinfunction "-IN_6") (pintype "input"))
      (node (ref "R47") (pin "2") (pinfunction "2_2") (pintype "passive"))
      (node (ref "R58") (pin "1") (pinfunction "1_1") (pintype "passive"))
    )
    (net (code "56") (name "Net-(IC9B-OUT)") (class "Default")
      (node (ref "IC9") (pin "7") (pinfunction "OUT_7") (pintype "output"))
      (node (ref "R42") (pin "2P") (pinfunction "S_2P") (pintype "passive"))
      (node (ref "R42") (pin "3P") (pinfunction "E_3P") (pintype "passive"))
      (node (ref "R53") (pin "2") (pinfunction "2_2") (pintype "passive"))
    )
    (net (code "57") (name "Net-(IC10A--IN)") (class "Default")
      (node (ref "C40") (pin "1") (pinfunction "1_1") (pintype "passive"))
      (node (ref "IC10") (pin "2") (pinfunction "-IN_2") (pintype "input"))
      (node (ref "R49") (pin "2") (pinfunction "2_2") (pintype "passive"))
      (node (ref "R51") (pin "1") (pinfunction "1_1") (pintype "passive"))
    )
    (net (code "58") (name "Net-(IC10A-OUT)") (class "Default")
      (node (ref "C40") (pin "2") (pinfunction "2_2") (pintype "passive"))
      (node (ref "IC10") (pin "1") (pinfunction "OUT_1") (pintype "output"))
      (node (ref "R49") (pin "1") (pinfunction "1_1") (pintype "passive"))
      (node (ref "R61") (pin "2") (pinfunction "2_2") (pintype "passive"))
    )
    (net (code "59") (name "Net-(IC10B--IN)") (class "Default")
      (node (ref "C42") (pin "1") (pinfunction "1_1") (pintype "passive"))
      (node (ref "IC10") (pin "6") (pinfunction "-IN_6") (pintype "input"))
      (node (ref "R48") (pin "2") (pinfunction "2_2") (pintype "passive"))
      (node (ref "R52") (pin "1") (pinfunction "1_1") (pintype "passive"))
    )
    (net (code "60") (name "Net-(IC10B-OUT)") (class "Default")
      (node (ref "C42") (pin "2") (pinfunction "2_2") (pintype "passive"))
      (node (ref "IC10") (pin "7") (pinfunction "OUT_7") (pintype "output"))
      (node (ref "R48") (pin "1") (pinfunction "1_1") (pintype "passive"))
      (node (ref "R62") (pin "2") (pinfunction "2_2") (pintype "passive"))
    )
    (net (code "61") (name "Net-(J1-3)") (class "Default")
      (node (ref "J1") (pin "P3") (pinfunction "3_P3") (pintype "passive"))
      (node (ref "R12") (pin "1") (pinfunction "1_1") (pintype "passive"))
    )
    (net (code "62") (name "Net-(J2-3)") (class "Default")
      (node (ref "J2") (pin "P3") (pinfunction "3_P3") (pintype "passive"))
      (node (ref "R15") (pin "1") (pinfunction "1_1") (pintype "passive"))
    )
    (net (code "63") (name "Net-(J3-3)") (class "Default")
      (node (ref "J3") (pin "P3") (pinfunction "3_P3") (pintype "passive"))
      (node (ref "R29") (pin "2") (pinfunction "2_2") (pintype "passive"))
    )
    (net (code "64") (name "Net-(J4-3)") (class "Default")
      (node (ref "J4") (pin "P3") (pinfunction "3_P3") (pintype "passive"))
      (node (ref "R21") (pin "2") (pinfunction "2_2") (pintype "passive"))
    )
    (net (code "65") (name "Net-(J5-3)") (class "Default")
      (node (ref "J5") (pin "P3") (pinfunction "3_P3") (pintype "passive"))
      (node (ref "R38") (pin "2") (pinfunction "2_2") (pintype "passive"))
    )
    (net (code "66") (name "Net-(J6-3)") (class "Default")
      (node (ref "J6") (pin "P3") (pinfunction "3_P3") (pintype "passive"))
      (node (ref "R39") (pin "2") (pinfunction "2_2") (pintype "passive"))
    )
    (net (code "67") (name "Net-(J7-3)") (class "Default")
      (node (ref "J7") (pin "P3") (pinfunction "3_P3") (pintype "passive"))
      (node (ref "J8") (pin "P2") (pinfunction "2_P2") (pintype "passive"))
      (node (ref "R57") (pin "2") (pinfunction "2_2") (pintype "passive"))
    )
    (net (code "68") (name "Net-(J8-3)") (class "Default")
      (node (ref "J8") (pin "P3") (pinfunction "3_P3") (pintype "passive"))
      (node (ref "R58") (pin "2") (pinfunction "2_2") (pintype "passive"))
    )
    (net (code "69") (name "Net-(J9-3)") (class "Default")
      (node (ref "J9") (pin "P3") (pinfunction "3_P3") (pintype "passive"))
      (node (ref "R32") (pin "2") (pinfunction "2_2") (pintype "passive"))
    )
    (net (code "70") (name "Net-(J10-3)") (class "Default")
      (node (ref "J10") (pin "P3") (pinfunction "3_P3") (pintype "passive"))
      (node (ref "R24") (pin "2") (pinfunction "2_2") (pintype "passive"))
    )
    (net (code "71") (name "Net-(J11-3)") (class "Default")
      (node (ref "J11") (pin "P3") (pinfunction "3_P3") (pintype "passive"))
      (node (ref "R61") (pin "1") (pinfunction "1_1") (pintype "passive"))
    )
    (net (code "72") (name "Net-(J12-3)") (class "Default")
      (node (ref "J12") (pin "P3") (pinfunction "3_P3") (pintype "passive"))
      (node (ref "R62") (pin "1") (pinfunction "1_1") (pintype "passive"))
    )
    (net (code "73") (name "Net-(LED1-GRN)") (class "Default")
      (node (ref "LED1") (pin "3") (pinfunction "GRN_3") (pintype "bidirectional"))
      (node (ref "R4") (pin "1") (pinfunction "1_1") (pintype "passive"))
    )
    (net (code "74") (name "Net-(LED1-RED)") (class "Default")
      (node (ref "LED1") (pin "1") (pinfunction "RED_1") (pintype "bidirectional"))
      (node (ref "R3") (pin "1") (pinfunction "1_1") (pintype "passive"))
    )
    (net (code "75") (name "Net-(LED2-GRN)") (class "Default")
      (node (ref "LED2") (pin "3") (pinfunction "GRN_3") (pintype "bidirectional"))
      (node (ref "R5") (pin "1") (pinfunction "1_1") (pintype "passive"))
    )
    (net (code "76") (name "Net-(LED2-RED)") (class "Default")
      (node (ref "LED2") (pin "1") (pinfunction "RED_1") (pintype "bidirectional"))
      (node (ref "R6") (pin "1") (pinfunction "1_1") (pintype "passive"))
    )
    (net (code "77") (name "Net-(LED3-GRN)") (class "Default")
      (node (ref "LED3") (pin "3") (pinfunction "GRN_3") (pintype "bidirectional"))
      (node (ref "R7") (pin "1") (pinfunction "1_1") (pintype "passive"))
    )
    (net (code "78") (name "Net-(LED3-RED)") (class "Default")
      (node (ref "LED3") (pin "1") (pinfunction "RED_1") (pintype "bidirectional"))
      (node (ref "R8") (pin "1") (pinfunction "1_1") (pintype "passive"))
    )
    (net (code "79") (name "Net-(LED4-GRN)") (class "Default")
      (node (ref "LED4") (pin "3") (pinfunction "GRN_3") (pintype "bidirectional"))
      (node (ref "R9") (pin "1") (pinfunction "1_1") (pintype "passive"))
    )
    (net (code "80") (name "Net-(LED4-RED)") (class "Default")
      (node (ref "LED4") (pin "1") (pinfunction "RED_1") (pintype "bidirectional"))
      (node (ref "R10") (pin "1") (pinfunction "1_1") (pintype "passive"))
    )
    (net (code "81") (name "Net-(Q1-PadB)") (class "Default")
      (node (ref "Q1") (pin "B") (pinfunction "B_B") (pintype "passive"))
      (node (ref "R12") (pin "2") (pinfunction "2_2") (pintype "passive"))
    )
    (net (code "82") (name "Net-(Q2-PadB)") (class "Default")
      (node (ref "Q2") (pin "B") (pinfunction "B_B") (pintype "passive"))
      (node (ref "R15") (pin "2") (pinfunction "2_2") (pintype "passive"))
    )
    (net (code "83") (name "Net-(R1-Pad2)") (class "Default")
      (node (ref "R1") (pin "2") (pinfunction "2_2") (pintype "passive"))
      (node (ref "R2") (pin "2") (pinfunction "2_2") (pintype "passive"))
      (node (ref "SW1") (pin "L1") (pinfunction "L1_L1") (pintype "passive"))
    )
    (net (code "84") (name "Net-(R18-S)") (class "Default")
      (node (ref "R18") (pin "P$2") (pinfunction "S_P$2") (pintype "passive"))
      (node (ref "R28") (pin "2") (pinfunction "2_2") (pintype "passive"))
    )
    (net (code "85") (name "Net-(R42A-A)") (class "Default")
      (node (ref "R42") (pin "1P") (pinfunction "A_1P") (pintype "passive"))
      (node (ref "R47") (pin "1") (pinfunction "1_1") (pintype "passive"))
    )
    (net (code "86") (name "Net-(R42B-A)") (class "Default")
      (node (ref "R42") (pin "1") (pinfunction "A_1") (pintype "passive"))
      (node (ref "R46") (pin "1") (pinfunction "1_1") (pintype "passive"))
    )
    (net (code "87") (name "Net-(R43-S)") (class "Default")
      (node (ref "R33") (pin "2") (pinfunction "2_2") (pintype "passive"))
      (node (ref "R43") (pin "P$2") (pinfunction "S_P$2") (pintype "passive"))
    )
    (net (code "88") (name "PITCH_POT") (class "Default")
      (node (ref "IC5") (pin "9") (pinfunction "PC1/ADC11_9") (pintype "bidirectional"))
      (node (ref "R20") (pin "P$2") (pinfunction "S_P$2") (pintype "passive"))
    )
    (net (code "89") (name "PLAY") (class "Default")
      (node (ref "IC5") (pin "58") (pinfunction "PB6/I2C1_SCL/TIM4_CH1/USART1_TX_58") (pintype "bidirectional"))
      (node (ref "Q2") (pin "C") (pinfunction "C_C") (pintype "passive"))
      (node (ref "R16") (pin "1") (pinfunction "1_1") (pintype "passive"))
    )
    (net (code "90") (name "POSITION_POT_CV") (class "Default")
      (node (ref "C9") (pin "2") (pinfunction "2_2") (pintype "passive"))
      (node (ref "IC3") (pin "7") (pinfunction "OUT_7") (pintype "output"))
      (node (ref "IC5") (pin "16") (pinfunction "PA2/USART2_TX/ADC2/TIM2_CH3_16") (pintype "bidirectional"))
      (node (ref "R27") (pin "1") (pinfunction "1_1") (pintype "passive"))
    )
    (net (code "91") (name "REC") (class "Default")
      (node (ref "IC5") (pin "59") (pinfunction "PB7/I2C1_SDA/TIM4_CH2/USART1_RX_59") (pintype "bidirectional"))
      (node (ref "Q1") (pin "C") (pinfunction "C_C") (pintype "passive"))
      (node (ref "R14") (pin "1") (pinfunction "1_1") (pintype "passive"))
    )
    (net (code "92") (name "RESET") (class "Default")
      (node (ref "IC5") (pin "7") (pinfunction "NRST_7") (pintype "bidirectional"))
      (node (ref "JP2") (pin "10") (pinfunction "10_10") (pintype "passive"))
      (node (ref "R17") (pin "1") (pinfunction "1_1") (pintype "passive"))
      (node (ref "SW5") (pin "B") (pinfunction "S_B") (pintype "passive"))
      (node (ref "SW5") (pin "B'") (pinfunction "S1_B'") (pintype "passive"))
    )
    (net (code "93") (name "RIN") (class "Default")
      (node (ref "C36") (pin "+") (pinfunction "+_+") (pintype "passive"))
      (node (ref "IC8") (pin "19") (pinfunction "RLINEIN_19") (pintype "bidirectional"))
    )
    (net (code "94") (name "ROUT") (class "Default")
      (node (ref "C41") (pin "+") (pinfunction "+_+") (pintype "passive"))
      (node (ref "IC8") (pin "13") (pinfunction "ROUT_13") (pintype "bidirectional"))
    )
    (net (code "95") (name "RX") (class "Default")
      (node (ref "IC5") (pin "43") (pinfunction "PA10/USART1_RX/TIM1_CH3_43") (pintype "bidirectional"))
      (node (ref "JP1") (pin "4") (pinfunction "4_4") (pintype "passive"))
    )
    (net (code "96") (name "SIZE_CV") (class "Default")
      (node (ref "C10") (pin "2") (pinfunction "2_2") (pintype "passive"))
      (node (ref "IC4") (pin "14") (pinfunction "OUT_14") (pintype "output"))
      (node (ref "IC5") (pin "15") (pinfunction "PA1/USART2_RTS/UART4_RX/ADC1/TIM2_CH2_15") (pintype "bidirectional"))
      (node (ref "R25") (pin "1") (pinfunction "1_1") (pintype "passive"))
    )
    (net (code "97") (name "SIZE_POT") (class "Default")
      (node (ref "IC5") (pin "8") (pinfunction "PC0/ADC10_8") (pintype "bidirectional"))
      (node (ref "R19") (pin "P$2") (pinfunction "S_P$2") (pintype "passive"))
    )
    (net (code "98") (name "SW_LOAD") (class "Default")
      (node (ref "IC5") (pin "51") (pinfunction "PC10/SPI3_SCK/I2S3_SCK/UART4_TX_51") (pintype "bidirectional"))
      (node (ref "SW3") (pin "3") (pinfunction "3_3") (pintype "passive"))
      (node (ref "SW3") (pin "4") (pinfunction "4_4") (pintype "passive"))
    )
    (net (code "99") (name "SW_MODE") (class "Default")
      (node (ref "IC5") (pin "52") (pinfunction "PC11/UART4_RX/SPI3_MISO/USART3_RX_52") (pintype "bidirectional"))
      (node (ref "SW2") (pin "3") (pinfunction "3_3") (pintype "passive"))
      (node (ref "SW2") (pin "4") (pinfunction "4_4") (pintype "passive"))
    )
    (net (code "100") (name "SW_REC") (class "Default")
      (node (ref "IC5") (pin "61") (pinfunction "PB8/TIM4_CH3/I2C1_SCL_61") (pintype "bidirectional"))
      (node (ref "SW1") (pin "P2") (pinfunction "A2_P2") (pintype "passive"))
      (node (ref "SW1") (pin "P5") (pinfunction "B2_P5") (pintype "passive"))
    )
    (net (code "101") (name "TEXTURE_CV") (class "Default")
      (node (ref "C11") (pin "2") (pinfunction "2_2") (pintype "passive"))
      (node (ref "IC4") (pin "8") (pinfunction "OUT_8") (pintype "output"))
      (node (ref "IC5") (pin "14") (pinfunction "PA0-WKUP/USART2_CTS/UART4_TX/ADC0/TIM2_CH1_ETR_14") (pintype "bidirectional"))
      (node (ref "R26") (pin "1") (pinfunction "1_1") (pintype "passive"))
    )
    (net (code "102") (name "TEXTURE_POT") (class "Default")
      (node (ref "IC5") (pin "22") (pinfunction "PA6/SPI1_MISO/ADC6/TIM3_CH1_22") (pintype "bidirectional"))
      (node (ref "R44") (pin "P$2") (pinfunction "S_P$2") (pintype "passive"))
    )
    (net (code "103") (name "TX") (class "Default")
      (node (ref "IC5") (pin "42") (pinfunction "PA9/USART1_TX/TIM1_CH2_42") (pintype "bidirectional"))
      (node (ref "JP1") (pin "5") (pinfunction "5_5") (pintype "passive"))
    )
    (net (code "104") (name "VBAT") (class "Default")
      (node (ref "IC5") (pin "1") (pinfunction "VBAT_1") (pintype "power_in"))
    )
    (net (code "105") (name "VCC") (class "Default")
      (node (ref "C1") (pin "+") (pinfunction "+_+") (pintype "passive"))
      (node (ref "C38") (pin "1") (pinfunction "1_1") (pintype "passive"))
      (node (ref "C39") (pin "1") (pinfunction "1_1") (pintype "passive"))
      (node (ref "D1") (pin "C") (pinfunction "C_C") (pintype "passive"))
      (node (ref "IC10") (pin "8") (pinfunction "V+_8") (pintype "power_in"))
      (node (ref "IC7") (pin "3") (pinfunction "VIN_3") (pintype "input"))
      (node (ref "IC9") (pin "8") (pinfunction "V+_8") (pintype "power_in"))
      (node (ref "R11") (pin "1") (pinfunction "1_1") (pintype "passive"))
    )
    (net (code "106") (name "VEE") (class "Default")
      (node (ref "C13") (pin "-") (pinfunction "-_-") (pintype "passive"))
      (node (ref "C45") (pin "2") (pinfunction "2_2") (pintype "passive"))
      (node (ref "C46") (pin "2") (pinfunction "2_2") (pintype "passive"))
      (node (ref "D2") (pin "A") (pinfunction "A_A") (pintype "passive"))
      (node (ref "IC10") (pin "4") (pinfunction "V-_4") (pintype "power_in"))
      (node (ref "IC9") (pin "4") (pinfunction "V-_4") (pintype "power_in"))
      (node (ref "R30") (pin "1") (pinfunction "1_1") (pintype "passive"))
    )
    (net (code "107") (name "V_OCT") (class "Default")
      (node (ref "C20") (pin "2") (pinfunction "2_2") (pintype "passive"))
      (node (ref "IC4") (pin "1") (pinfunction "OUT_1") (pintype "output"))
      (node (ref "IC5") (pin "20") (pinfunction "PA4/SPI1_NSS/SPI3_NSS/USART2_CK/I2S3_WS/ADC4/DAC1_20") (pintype "bidirectional"))
      (node (ref "R34") (pin "1") (pinfunction "1_1") (pintype "passive"))
    )
    (net (code "108") (name "unconnected-(IC1A-QH*-Pad9)") (class "Default")
      (node (ref "IC1") (pin "9") (pinfunction "QH*_9") (pintype "tri_state"))
    )
    (net (code "109") (name "unconnected-(IC5-PA8{slash}USART1_CK{slash}TIM1_CH1{slash}MCO-Pad41)") (class "Default")
      (node (ref "IC5") (pin "41") (pinfunction "PA8/USART1_CK/TIM1_CH1/MCO_41") (pintype "bidirectional"))
    )
    (net (code "110") (name "unconnected-(IC5-PA11{slash}USART1_CTS{slash}CANRX{slash}USBDM{slash}TIM1_CH4-Pad44)") (class "Default")
      (node (ref "IC5") (pin "44") (pinfunction "PA11/USART1_CTS/CANRX/USBDM/TIM1_CH4_44") (pintype "bidirectional"))
    )
    (net (code "111") (name "unconnected-(IC5-PA12{slash}USART1_RTS{slash}CANTX{slash}USBDP{slash}TIM1_ETR-Pad45)") (class "Default")
      (node (ref "IC5") (pin "45") (pinfunction "PA12/USART1_RTS/CANTX/USBDP/TIM1_ETR_45") (pintype "bidirectional"))
    )
    (net (code "112") (name "unconnected-(IC5-PB1{slash}ADC9{slash}TIM3_CH4-Pad27)") (class "Default")
      (node (ref "IC5") (pin "27") (pinfunction "PB1/ADC9/TIM3_CH4_27") (pintype "bidirectional"))
    )
    (net (code "113") (name "unconnected-(IC5-PB4{slash}NJTRST{slash}SPI3_MISO{slash}SPI1_MISO-Pad56)") (class "Default")
      (node (ref "IC5") (pin "56") (pinfunction "PB4/NJTRST/SPI3_MISO/SPI1_MISO_56") (pintype "bidirectional"))
    )
    (net (code "114") (name "unconnected-(IC5-PC2{slash}SPI2_MISO{slash}ADC12-Pad10)") (class "Default")
      (node (ref "IC5") (pin "10") (pinfunction "PC2/SPI2_MISO/ADC12_10") (pintype "bidirectional"))
    )
    (net (code "115") (name "unconnected-(IC5-PC3{slash}SPI2_MOSI{slash}I2S2_SD{slash}ADC13-Pad11)") (class "Default")
      (node (ref "IC5") (pin "11") (pinfunction "PC3/SPI2_MOSI/I2S2_SD/ADC13_11") (pintype "bidirectional"))
    )
    (net (code "116") (name "unconnected-(IC5-PC6{slash}I2S2_MCK-Pad37)") (class "Default")
      (node (ref "IC5") (pin "37") (pinfunction "PC6/I2S2_MCK_37") (pintype "bidirectional"))
    )
    (net (code "117") (name "unconnected-(IC5-PC7{slash}I2S3_MCK-Pad38)") (class "Default")
      (node (ref "IC5") (pin "38") (pinfunction "PC7/I2S3_MCK_38") (pintype "bidirectional"))
    )
    (net (code "118") (name "unconnected-(IC5-PC8-Pad39)") (class "Default")
      (node (ref "IC5") (pin "39") (pinfunction "PC8_39") (pintype "bidirectional"))
    )
    (net (code "119") (name "unconnected-(IC5-PC9{slash}I2S2_CKIN{slash}I2S3_CKIN-Pad40)") (class "Default")
      (node (ref "IC5") (pin "40") (pinfunction "PC9/I2S2_CKIN/I2S3_CKIN_40") (pintype "bidirectional"))
    )
    (net (code "120") (name "unconnected-(IC5-PC12{slash}UART5_TX{slash}I2S3_SD{slash}USART3_CK-Pad53)") (class "Default")
      (node (ref "IC5") (pin "53") (pinfunction "PC12/UART5_TX/I2S3_SD/USART3_CK_53") (pintype "bidirectional"))
    )
    (net (code "121") (name "unconnected-(IC5-PC13-TAMPER-RTC-Pad2)") (class "Default")
      (node (ref "IC5") (pin "2") (pinfunction "PC13-TAMPER-RTC_2") (pintype "bidirectional"))
    )
    (net (code "122") (name "unconnected-(IC5-PC14{slash}OSC32_IN-Pad3)") (class "Default")
      (node (ref "IC5") (pin "3") (pinfunction "PC14/OSC32_IN_3") (pintype "bidirectional"))
    )
    (net (code "123") (name "unconnected-(IC5-PC15{slash}OSC_OUT-Pad4)") (class "Default")
      (node (ref "IC5") (pin "4") (pinfunction "PC15/OSC_OUT_4") (pintype "bidirectional"))
    )
    (net (code "124") (name "unconnected-(IC5-PD2{slash}TIM3-ETR-Pad54)") (class "Default")
      (node (ref "IC5") (pin "54") (pinfunction "PD2/TIM3-ETR_54") (pintype "bidirectional"))
    )
    (net (code "125") (name "unconnected-(IC8-CLKOUT-Pad2)") (class "Default")
      (node (ref "IC8") (pin "2") (pinfunction "CLKOUT_2") (pintype "bidirectional"))
    )
    (net (code "126") (name "unconnected-(IC8-LHPOUT-Pad9)") (class "Default")
      (node (ref "IC8") (pin "9") (pinfunction "LHPOUT_9") (pintype "bidirectional"))
    )
    (net (code "127") (name "unconnected-(IC8-MICBIAS-Pad17)") (class "Default")
      (node (ref "IC8") (pin "17") (pinfunction "MICBIAS_17") (pintype "bidirectional"))
    )
    (net (code "128") (name "unconnected-(IC8-MICIN-Pad18)") (class "Default")
      (node (ref "IC8") (pin "18") (pinfunction "MICIN_18") (pintype "bidirectional"))
    )
    (net (code "129") (name "unconnected-(IC8-RHPOUT-Pad10)") (class "Default")
      (node (ref "IC8") (pin "10") (pinfunction "RHPOUT_10") (pintype "bidirectional"))
    )
    (net (code "130") (name "unconnected-(J3-2-PadP2)") (class "Default")
      (node (ref "J3") (pin "P2") (pinfunction "2_P2") (pintype "passive"))
    )
    (net (code "131") (name "unconnected-(J4-2-PadP2)") (class "Default")
      (node (ref "J4") (pin "P2") (pinfunction "2_P2") (pintype "passive"))
    )
    (net (code "132") (name "unconnected-(J5-2-PadP2)") (class "Default")
      (node (ref "J5") (pin "P2") (pinfunction "2_P2") (pintype "passive"))
    )
    (net (code "133") (name "unconnected-(J6-2-PadP2)") (class "Default")
      (node (ref "J6") (pin "P2") (pinfunction "2_P2") (pintype "passive"))
    )
    (net (code "134") (name "unconnected-(J7-2-PadP2)") (class "Default")
      (node (ref "J7") (pin "P2") (pinfunction "2_P2") (pintype "passive"))
    )
    (net (code "135") (name "unconnected-(J9-2-PadP2)") (class "Default")
      (node (ref "J9") (pin "P2") (pinfunction "2_P2") (pintype "passive"))
    )
    (net (code "136") (name "unconnected-(J10-2-PadP2)") (class "Default")
      (node (ref "J10") (pin "P2") (pinfunction "2_P2") (pintype "passive"))
    )
    (net (code "137") (name "unconnected-(J11-2-PadP2)") (class "Default")
      (node (ref "J11") (pin "P2") (pinfunction "2_P2") (pintype "passive"))
    )
    (net (code "138") (name "unconnected-(J12-2-PadP2)") (class "Default")
      (node (ref "J12") (pin "P2") (pinfunction "2_P2") (pintype "passive"))
    )
    (net (code "139") (name "unconnected-(JP1-Pad2)") (class "Default")
      (node (ref "JP1") (pin "2") (pinfunction "2_2") (pintype "passive"))
    )
    (net (code "140") (name "unconnected-(JP1-Pad3)") (class "Default")
      (node (ref "JP1") (pin "3") (pinfunction "3_3") (pintype "passive"))
    )
    (net (code "141") (name "unconnected-(JP1-Pad6)") (class "Default")
      (node (ref "JP1") (pin "6") (pinfunction "6_6") (pintype "passive"))
    )
    (net (code "142") (name "unconnected-(JP2-Pad7)") (class "Default")
      (node (ref "JP2") (pin "7") (pinfunction "7_7") (pintype "passive"))
    )
    (net (code "143") (name "unconnected-(SW1A-A1-PadP1)") (class "Default")
      (node (ref "SW1") (pin "P1") (pinfunction "A1_P1") (pintype "passive"))
    )
    (net (code "144") (name "unconnected-(SW1A-B1-PadP4)") (class "Default")
      (node (ref "SW1") (pin "P4") (pinfunction "B1_P4") (pintype "passive"))
    )
  )
)
